# xxxxxx_PCB_Spectrum_Analyzer_x.net
KiCad netlist of a schematic drawn in Altium Designer
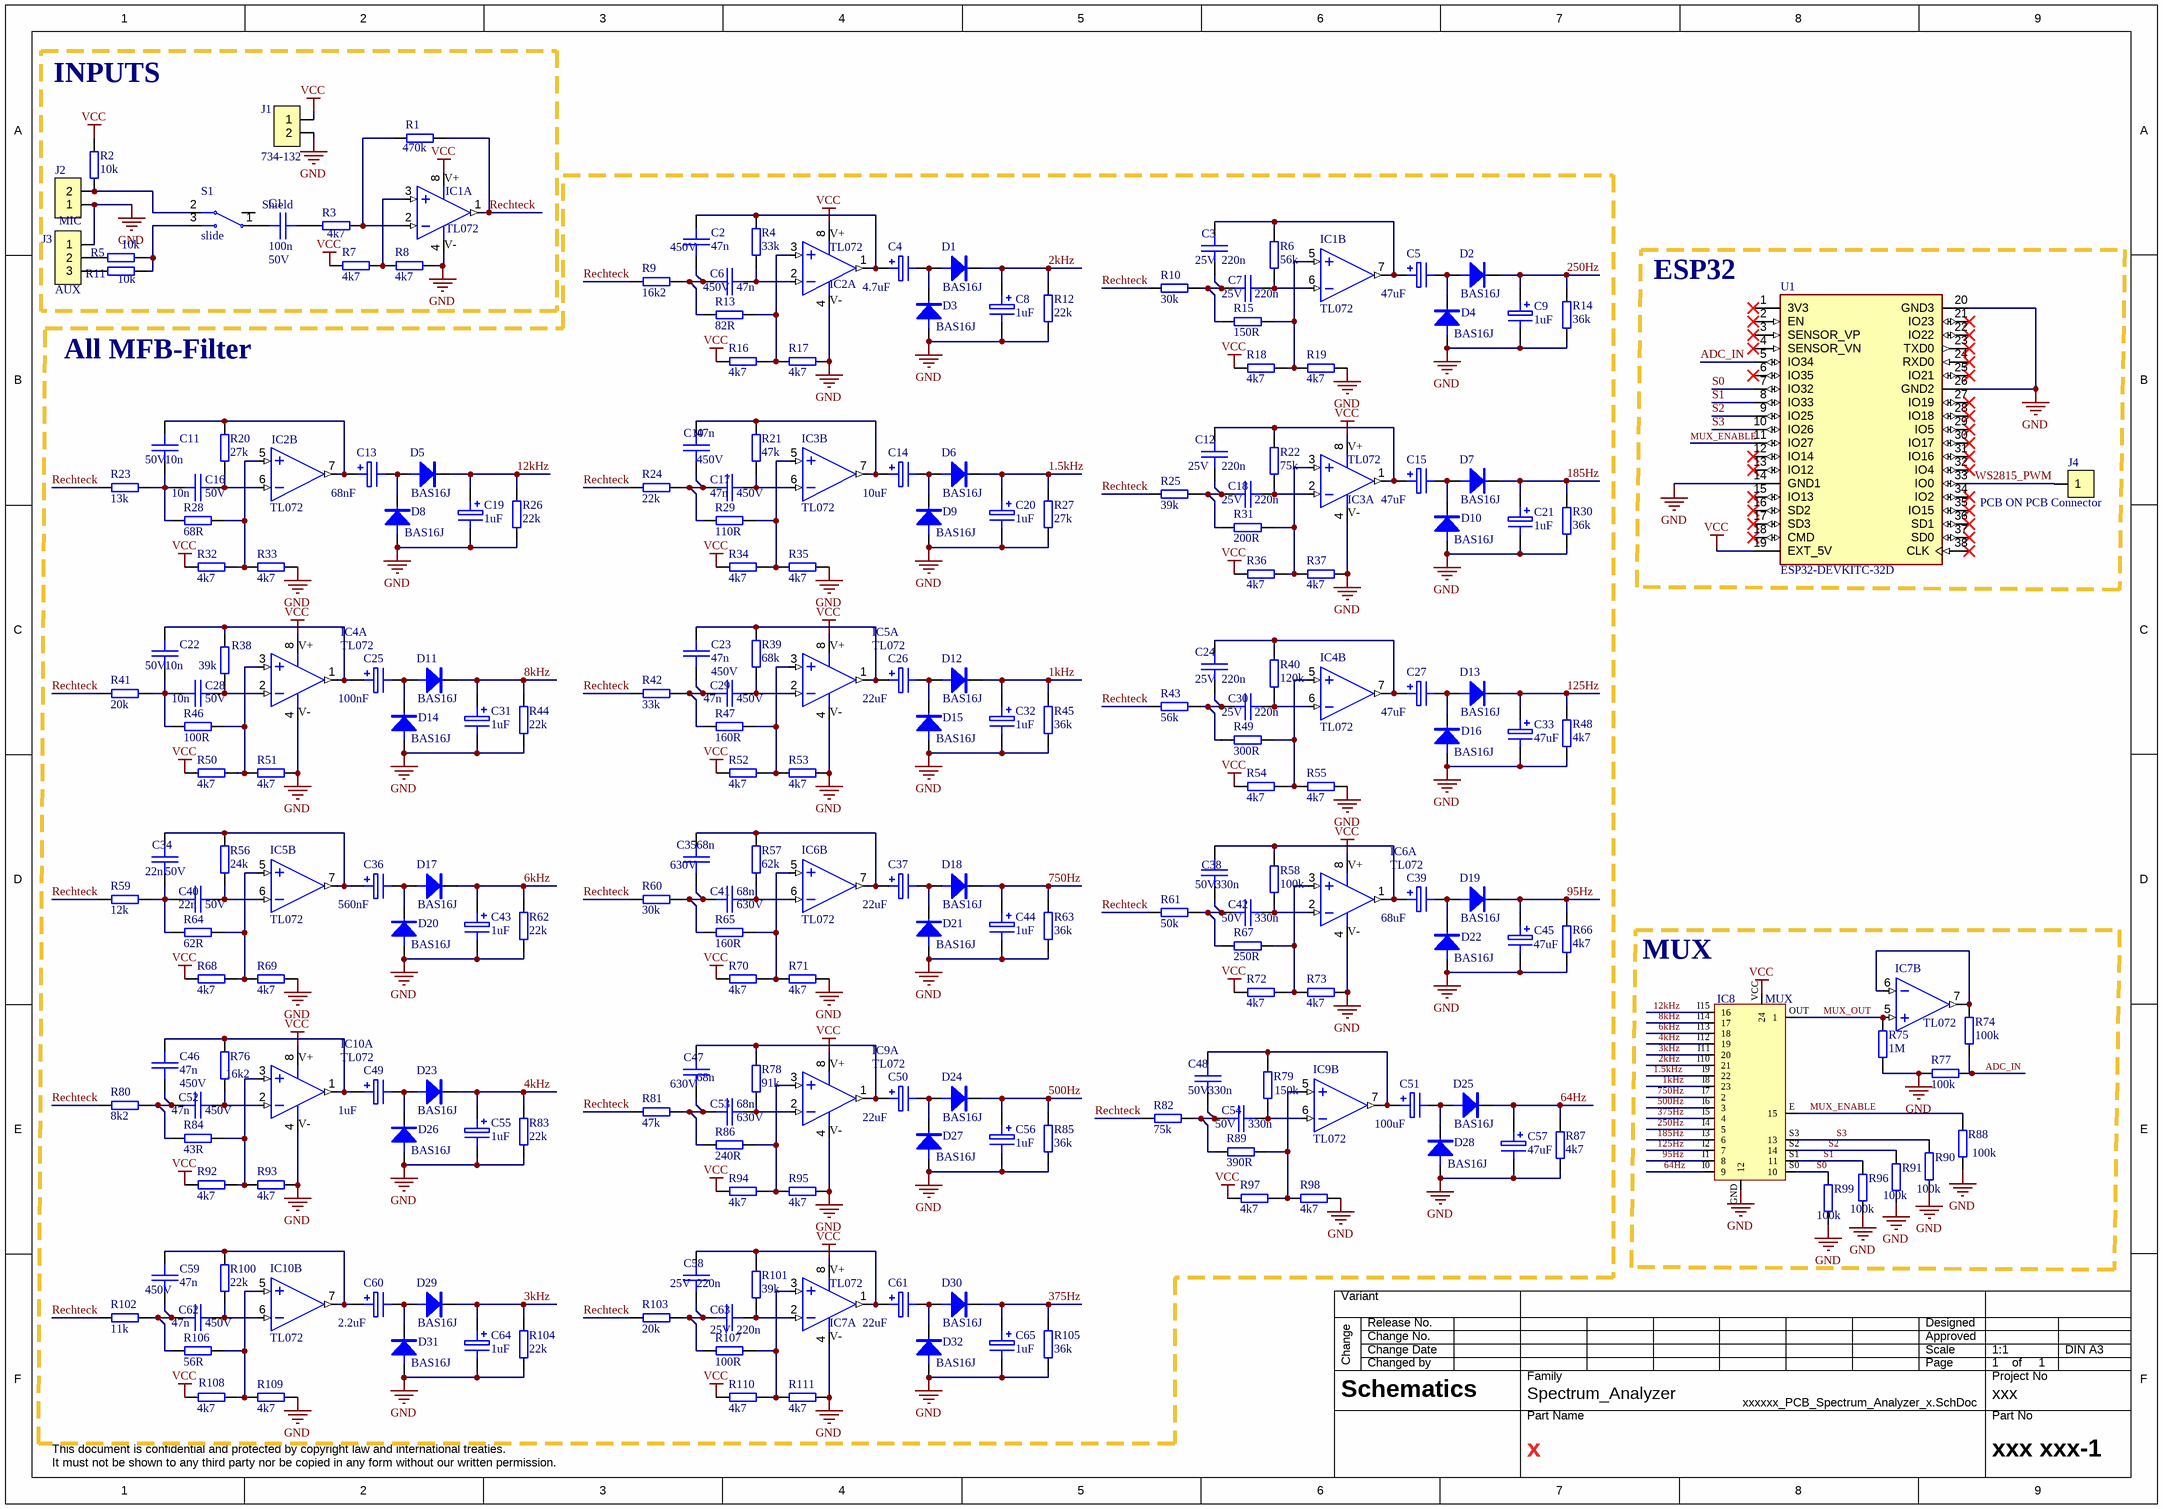
[diagram p0: xxxxxx_PCB_Spectrum_Analyzer_x.SchDoc]

(export (version "E")
  (design (tool "Eeschema 10.0.6"))
  (components
    (comp (ref "C1")
      (value "100n")
      (footprint "C_0805_B")
      (description "C 100n 10% 50V X7R 0805")
      (fields
        (field (name "U") "50V")
        (field (name "PART NUMBER") "301 143")
        (field (name "PUBLISHER") "RKE")
      )
      (libsource (lib "SMD") (part "Capacitor"))
    )
    (comp (ref "C2")
      (value "47n")
      (footprint "C_0805_C")
      (description "C 47n 10% 450V X7T 0805")
      (fields
        (field (name "U") "450V")
        (field (name "PART NUMBER") "302 687")
        (field (name "PUBLISHER") "RKE")
      )
      (libsource (lib "SMD") (part "Capacitor"))
    )
    (comp (ref "C3")
      (value "220n")
      (footprint "C_1206_C")
      (description "C 220n 20% 25V X7R 1206")
      (fields
        (field (name "U") "25V")
        (field (name "PART NUMBER") "301 734")
        (field (name "PUBLISHER") "RKE")
      )
      (libsource (lib "SMD") (part "Capacitor"))
    )
    (comp (ref "C4") (value "4.7uF") (footprint "C 4.7uF") (libsource (lib "4.7 uF") (part "C 4.7uF 450V")))
    (comp (ref "C5") (value "47uF") (footprint "C 4.7uF") (libsource (lib "4.7 uF") (part "C 4.7uF 450V")))
    (comp (ref "C6")
      (value "47n")
      (footprint "C_0805_C")
      (description "C 47n 10% 450V X7T 0805")
      (fields
        (field (name "U") "450V")
        (field (name "PART NUMBER") "302 687")
        (field (name "PUBLISHER") "RKE")
      )
      (libsource (lib "SMD") (part "Capacitor"))
    )
    (comp (ref "C7")
      (value "220n")
      (footprint "C_1206_C")
      (description "C 220n 20% 25V X7R 1206")
      (fields
        (field (name "U") "25V")
        (field (name "PART NUMBER") "301 734")
        (field (name "PUBLISHER") "RKE")
      )
      (libsource (lib "SMD") (part "Capacitor"))
    )
    (comp (ref "C8") (value "1uF") (footprint "C 4.7uF") (libsource (lib "4.7 uF") (part "C 4.7uF 450V")))
    (comp (ref "C9") (value "1uF") (footprint "C 4.7uF") (libsource (lib "4.7 uF") (part "C 4.7uF 450V")))
    (comp (ref "C10")
      (value "47n")
      (footprint "C_0805_C")
      (description "C 47n 10% 450V X7T 0805")
      (fields
        (field (name "U") "450V")
        (field (name "PART NUMBER") "302 687")
        (field (name "PUBLISHER") "RKE")
      )
      (libsource (lib "SMD") (part "Capacitor"))
    )
    (comp (ref "C11")
      (value "10n")
      (footprint "C_0805_B")
      (description "C 10n 10% 50V X7R 0805")
      (fields
        (field (name "U") "50V")
        (field (name "PART NUMBER") "300 130")
        (field (name "PUBLISHER") "RKE")
      )
      (libsource (lib "SMD") (part "Capacitor"))
    )
    (comp (ref "C12")
      (value "220n")
      (footprint "C_1206_C")
      (description "C 220n 20% 25V X7R 1206")
      (fields
        (field (name "U") "25V")
        (field (name "PART NUMBER") "301 734")
        (field (name "PUBLISHER") "RKE")
      )
      (libsource (lib "SMD") (part "Capacitor"))
    )
    (comp (ref "C13") (value "68nF") (footprint "C 4.7uF") (libsource (lib "4.7 uF") (part "C 4.7uF 450V")))
    (comp (ref "C14") (value "10uF") (footprint "C 4.7uF") (libsource (lib "4.7 uF") (part "C 4.7uF 450V")))
    (comp (ref "C15") (value "47uF") (footprint "C 4.7uF") (libsource (lib "4.7 uF") (part "C 4.7uF 450V")))
    (comp (ref "C16")
      (value "10n")
      (footprint "C_0805_B")
      (description "C 10n 10% 50V X7R 0805")
      (fields
        (field (name "U") "50V")
        (field (name "PART NUMBER") "300 130")
        (field (name "PUBLISHER") "RKE")
      )
      (libsource (lib "SMD") (part "Capacitor"))
    )
    (comp (ref "C17")
      (value "47n")
      (footprint "C_0805_C")
      (description "C 47n 10% 450V X7T 0805")
      (fields
        (field (name "U") "450V")
        (field (name "PART NUMBER") "302 687")
        (field (name "PUBLISHER") "RKE")
      )
      (libsource (lib "SMD") (part "Capacitor"))
    )
    (comp (ref "C18")
      (value "220n")
      (footprint "C_1206_C")
      (description "C 220n 20% 25V X7R 1206")
      (fields
        (field (name "U") "25V")
        (field (name "PART NUMBER") "301 734")
        (field (name "PUBLISHER") "RKE")
      )
      (libsource (lib "SMD") (part "Capacitor"))
    )
    (comp (ref "C19") (value "1uF") (footprint "C 4.7uF") (libsource (lib "4.7 uF") (part "C 4.7uF 450V")))
    (comp (ref "C20") (value "1uF") (footprint "C 4.7uF") (libsource (lib "4.7 uF") (part "C 4.7uF 450V")))
    (comp (ref "C21") (value "1uF") (footprint "C 4.7uF") (libsource (lib "4.7 uF") (part "C 4.7uF 450V")))
    (comp (ref "C22")
      (value "10n")
      (footprint "C_0805_B")
      (description "C 10n 10% 50V X7R 0805")
      (fields
        (field (name "U") "50V")
        (field (name "PART NUMBER") "300 130")
        (field (name "PUBLISHER") "RKE")
      )
      (libsource (lib "SMD") (part "Capacitor"))
    )
    (comp (ref "C23")
      (value "47n")
      (footprint "C_0805_C")
      (description "C 47n 10% 450V X7T 0805")
      (fields
        (field (name "U") "450V")
        (field (name "PART NUMBER") "302 687")
        (field (name "PUBLISHER") "RKE")
      )
      (libsource (lib "SMD") (part "Capacitor"))
    )
    (comp (ref "C24")
      (value "220n")
      (footprint "C_1206_C")
      (description "C 220n 20% 25V X7R 1206")
      (fields
        (field (name "U") "25V")
        (field (name "PART NUMBER") "301 734")
        (field (name "PUBLISHER") "RKE")
      )
      (libsource (lib "SMD") (part "Capacitor"))
    )
    (comp (ref "C25") (value "100nF") (footprint "C 4.7uF") (libsource (lib "4.7 uF") (part "C 4.7uF 450V")))
    (comp (ref "C26") (value "22uF") (footprint "C 4.7uF") (libsource (lib "4.7 uF") (part "C 4.7uF 450V")))
    (comp (ref "C27") (value "47uF") (footprint "C 4.7uF") (libsource (lib "4.7 uF") (part "C 4.7uF 450V")))
    (comp (ref "C28")
      (value "10n")
      (footprint "C_0805_B")
      (description "C 10n 10% 50V X7R 0805")
      (fields
        (field (name "U") "50V")
        (field (name "PART NUMBER") "300 130")
        (field (name "PUBLISHER") "RKE")
      )
      (libsource (lib "SMD") (part "Capacitor"))
    )
    (comp (ref "C29")
      (value "47n")
      (footprint "C_0805_C")
      (description "C 47n 10% 450V X7T 0805")
      (fields
        (field (name "U") "450V")
        (field (name "PART NUMBER") "302 687")
        (field (name "PUBLISHER") "RKE")
      )
      (libsource (lib "SMD") (part "Capacitor"))
    )
    (comp (ref "C30")
      (value "220n")
      (footprint "C_1206_C")
      (description "C 220n 20% 25V X7R 1206")
      (fields
        (field (name "U") "25V")
        (field (name "PART NUMBER") "301 734")
        (field (name "PUBLISHER") "RKE")
      )
      (libsource (lib "SMD") (part "Capacitor"))
    )
    (comp (ref "C31") (value "1uF") (footprint "C 4.7uF") (libsource (lib "4.7 uF") (part "C 4.7uF 450V")))
    (comp (ref "C32") (value "1uF") (footprint "C 4.7uF") (libsource (lib "4.7 uF") (part "C 4.7uF 450V")))
    (comp (ref "C33") (value "47uF") (footprint "C 4.7uF") (libsource (lib "4.7 uF") (part "C 4.7uF 450V")))
    (comp (ref "C34")
      (value "22n")
      (footprint "C_0805_A")
      (description "C 22n 10% 50V X7R 0805")
      (fields
        (field (name "U") "50V")
        (field (name "PART NUMBER") "300 131")
        (field (name "PUBLISHER") "RKE")
      )
      (libsource (lib "SMD") (part "Capacitor"))
    )
    (comp (ref "C35")
      (value "68n")
      (footprint "C_1210_D")
      (description "C 68n 20% 630V X7R 1210")
      (fields
        (field (name "U") "630V")
        (field (name "PART NUMBER") "302 807")
        (field (name "PUBLISHER") "RKE")
      )
      (libsource (lib "SMD") (part "Capacitor"))
    )
    (comp (ref "C36") (value "560nF") (footprint "C 4.7uF") (libsource (lib "4.7 uF") (part "C 4.7uF 450V")))
    (comp (ref "C37") (value "22uF") (footprint "C 4.7uF") (libsource (lib "4.7 uF") (part "C 4.7uF 450V")))
    (comp (ref "C38")
      (value "330n")
      (footprint "C_1210_D")
      (description "C 330n 50V X7R 1210")
      (fields
        (field (name "U") "50V")
        (field (name "PART NUMBER") "300 462")
        (field (name "PUBLISHER") "RKE")
      )
      (libsource (lib "SMD") (part "Capacitor"))
    )
    (comp (ref "C39") (value "68uF") (footprint "C 4.7uF") (libsource (lib "4.7 uF") (part "C 4.7uF 450V")))
    (comp (ref "C40")
      (value "22n")
      (footprint "C_0805_A")
      (description "C 22n 10% 50V X7R 0805")
      (fields
        (field (name "U") "50V")
        (field (name "PART NUMBER") "300 131")
        (field (name "PUBLISHER") "RKE")
      )
      (libsource (lib "SMD") (part "Capacitor"))
    )
    (comp (ref "C41")
      (value "68n")
      (footprint "C_1210_D")
      (description "C 68n 20% 630V X7R 1210")
      (fields
        (field (name "U") "630V")
        (field (name "PART NUMBER") "302 807")
        (field (name "PUBLISHER") "RKE")
      )
      (libsource (lib "SMD") (part "Capacitor"))
    )
    (comp (ref "C42")
      (value "330n")
      (footprint "C_1210_D")
      (description "C 330n 50V X7R 1210")
      (fields
        (field (name "U") "50V")
        (field (name "PART NUMBER") "300 462")
        (field (name "PUBLISHER") "RKE")
      )
      (libsource (lib "SMD") (part "Capacitor"))
    )
    (comp (ref "C43") (value "1uF") (footprint "C 4.7uF") (libsource (lib "4.7 uF") (part "C 4.7uF 450V")))
    (comp (ref "C44") (value "1uF") (footprint "C 4.7uF") (libsource (lib "4.7 uF") (part "C 4.7uF 450V")))
    (comp (ref "C45") (value "47uF") (footprint "C 4.7uF") (libsource (lib "4.7 uF") (part "C 4.7uF 450V")))
    (comp (ref "C46")
      (value "47n")
      (footprint "C_0805_C")
      (description "C 47n 10% 450V X7T 0805")
      (fields
        (field (name "U") "450V")
        (field (name "PART NUMBER") "302 687")
        (field (name "PUBLISHER") "RKE")
      )
      (libsource (lib "SMD") (part "Capacitor"))
    )
    (comp (ref "C47")
      (value "68n")
      (footprint "C_1210_D")
      (description "C 68n 20% 630V X7R 1210")
      (fields
        (field (name "U") "630V")
        (field (name "PART NUMBER") "302 807")
        (field (name "PUBLISHER") "RKE")
      )
      (libsource (lib "SMD") (part "Capacitor"))
    )
    (comp (ref "C48")
      (value "330n")
      (footprint "C_1210_D")
      (description "C 330n 50V X7R 1210")
      (fields
        (field (name "U") "50V")
        (field (name "PART NUMBER") "300 462")
        (field (name "PUBLISHER") "RKE")
      )
      (libsource (lib "SMD") (part "Capacitor"))
    )
    (comp (ref "C49") (value "1uF") (footprint "C 4.7uF") (libsource (lib "4.7 uF") (part "C 4.7uF 450V")))
    (comp (ref "C50") (value "22uF") (footprint "C 4.7uF") (libsource (lib "4.7 uF") (part "C 4.7uF 450V")))
    (comp (ref "C51") (value "100uF") (footprint "C 4.7uF") (libsource (lib "4.7 uF") (part "C 4.7uF 450V")))
    (comp (ref "C52")
      (value "47n")
      (footprint "C_0805_C")
      (description "C 47n 10% 450V X7T 0805")
      (fields
        (field (name "U") "450V")
        (field (name "PART NUMBER") "302 687")
        (field (name "PUBLISHER") "RKE")
      )
      (libsource (lib "SMD") (part "Capacitor"))
    )
    (comp (ref "C53")
      (value "68n")
      (footprint "C_1210_D")
      (description "C 68n 20% 630V X7R 1210")
      (fields
        (field (name "U") "630V")
        (field (name "PART NUMBER") "302 807")
        (field (name "PUBLISHER") "RKE")
      )
      (libsource (lib "SMD") (part "Capacitor"))
    )
    (comp (ref "C54")
      (value "330n")
      (footprint "C_1210_D")
      (description "C 330n 50V X7R 1210")
      (fields
        (field (name "U") "50V")
        (field (name "PART NUMBER") "300 462")
        (field (name "PUBLISHER") "RKE")
      )
      (libsource (lib "SMD") (part "Capacitor"))
    )
    (comp (ref "C55") (value "1uF") (footprint "C 4.7uF") (libsource (lib "4.7 uF") (part "C 4.7uF 450V")))
    (comp (ref "C56") (value "1uF") (footprint "C 4.7uF") (libsource (lib "4.7 uF") (part "C 4.7uF 450V")))
    (comp (ref "C57") (value "47uF") (footprint "C 4.7uF") (libsource (lib "4.7 uF") (part "C 4.7uF 450V")))
    (comp (ref "C58")
      (value "220n")
      (footprint "C_1206_C")
      (description "C 220n 20% 25V X7R 1206")
      (fields
        (field (name "U") "25V")
        (field (name "PART NUMBER") "301 734")
        (field (name "PUBLISHER") "RKE")
      )
      (libsource (lib "SMD") (part "Capacitor"))
    )
    (comp (ref "C59")
      (value "47n")
      (footprint "C_0805_C")
      (description "C 47n 10% 450V X7T 0805")
      (fields
        (field (name "U") "450V")
        (field (name "PART NUMBER") "302 687")
        (field (name "PUBLISHER") "RKE")
      )
      (libsource (lib "SMD") (part "Capacitor"))
    )
    (comp (ref "C60") (value "2.2uF") (footprint "C 4.7uF") (libsource (lib "4.7 uF") (part "C 4.7uF 450V")))
    (comp (ref "C61") (value "22uF") (footprint "C 4.7uF") (libsource (lib "4.7 uF") (part "C 4.7uF 450V")))
    (comp (ref "C62")
      (value "47n")
      (footprint "C_0805_C")
      (description "C 47n 10% 450V X7T 0805")
      (fields
        (field (name "U") "450V")
        (field (name "PART NUMBER") "302 687")
        (field (name "PUBLISHER") "RKE")
      )
      (libsource (lib "SMD") (part "Capacitor"))
    )
    (comp (ref "C63")
      (value "220n")
      (footprint "C_1206_C")
      (description "C 220n 20% 25V X7R 1206")
      (fields
        (field (name "U") "25V")
        (field (name "PART NUMBER") "301 734")
        (field (name "PUBLISHER") "RKE")
      )
      (libsource (lib "SMD") (part "Capacitor"))
    )
    (comp (ref "C64") (value "1uF") (footprint "C 4.7uF") (libsource (lib "4.7 uF") (part "C 4.7uF 450V")))
    (comp (ref "C65") (value "1uF") (footprint "C 4.7uF") (libsource (lib "4.7 uF") (part "C 4.7uF 450V")))
    (comp (ref "D1")
      (value "~")
      (footprint "SOD323F")
      (description "D BAS16J 250mA/100V SOD323F")
      (fields
        (field (name "PART") "BAS16J")
        (field (name "PART NUMBER") "303 357")
        (field (name "MANNUFACTURERPARTNUMBER") "BAS16J")
        (field (name "PUBLISHER") "MFL")
      )
      (libsource (lib "SMD") (part "Diode"))
    )
    (comp (ref "D2")
      (value "~")
      (footprint "SOD323F")
      (description "D BAS16J 250mA/100V SOD323F")
      (fields
        (field (name "PART") "BAS16J")
        (field (name "PART NUMBER") "303 357")
        (field (name "MANNUFACTURERPARTNUMBER") "BAS16J")
        (field (name "PUBLISHER") "MFL")
      )
      (libsource (lib "SMD") (part "Diode"))
    )
    (comp (ref "D3")
      (value "~")
      (footprint "SOD323F")
      (description "D BAS16J 250mA/100V SOD323F")
      (fields
        (field (name "PART") "BAS16J")
        (field (name "PART NUMBER") "303 357")
        (field (name "MANNUFACTURERPARTNUMBER") "BAS16J")
        (field (name "PUBLISHER") "MFL")
      )
      (libsource (lib "SMD") (part "Diode"))
    )
    (comp (ref "D4")
      (value "~")
      (footprint "SOD323F")
      (description "D BAS16J 250mA/100V SOD323F")
      (fields
        (field (name "PART") "BAS16J")
        (field (name "PART NUMBER") "303 357")
        (field (name "MANNUFACTURERPARTNUMBER") "BAS16J")
        (field (name "PUBLISHER") "MFL")
      )
      (libsource (lib "SMD") (part "Diode"))
    )
    (comp (ref "D5")
      (value "~")
      (footprint "SOD323F")
      (description "D BAS16J 250mA/100V SOD323F")
      (fields
        (field (name "PART") "BAS16J")
        (field (name "PART NUMBER") "303 357")
        (field (name "MANNUFACTURERPARTNUMBER") "BAS16J")
        (field (name "PUBLISHER") "MFL")
      )
      (libsource (lib "SMD") (part "Diode"))
    )
    (comp (ref "D6")
      (value "~")
      (footprint "SOD323F")
      (description "D BAS16J 250mA/100V SOD323F")
      (fields
        (field (name "PART") "BAS16J")
        (field (name "PART NUMBER") "303 357")
        (field (name "MANNUFACTURERPARTNUMBER") "BAS16J")
        (field (name "PUBLISHER") "MFL")
      )
      (libsource (lib "SMD") (part "Diode"))
    )
    (comp (ref "D7")
      (value "~")
      (footprint "SOD323F")
      (description "D BAS16J 250mA/100V SOD323F")
      (fields
        (field (name "PART") "BAS16J")
        (field (name "PART NUMBER") "303 357")
        (field (name "MANNUFACTURERPARTNUMBER") "BAS16J")
        (field (name "PUBLISHER") "MFL")
      )
      (libsource (lib "SMD") (part "Diode"))
    )
    (comp (ref "D8")
      (value "~")
      (footprint "SOD323F")
      (description "D BAS16J 250mA/100V SOD323F")
      (fields
        (field (name "PART") "BAS16J")
        (field (name "PART NUMBER") "303 357")
        (field (name "MANNUFACTURERPARTNUMBER") "BAS16J")
        (field (name "PUBLISHER") "MFL")
      )
      (libsource (lib "SMD") (part "Diode"))
    )
    (comp (ref "D9")
      (value "~")
      (footprint "SOD323F")
      (description "D BAS16J 250mA/100V SOD323F")
      (fields
        (field (name "PART") "BAS16J")
        (field (name "PART NUMBER") "303 357")
        (field (name "MANNUFACTURERPARTNUMBER") "BAS16J")
        (field (name "PUBLISHER") "MFL")
      )
      (libsource (lib "SMD") (part "Diode"))
    )
    (comp (ref "D10")
      (value "~")
      (footprint "SOD323F")
      (description "D BAS16J 250mA/100V SOD323F")
      (fields
        (field (name "PART") "BAS16J")
        (field (name "PART NUMBER") "303 357")
        (field (name "MANNUFACTURERPARTNUMBER") "BAS16J")
        (field (name "PUBLISHER") "MFL")
      )
      (libsource (lib "SMD") (part "Diode"))
    )
    (comp (ref "D11")
      (value "~")
      (footprint "SOD323F")
      (description "D BAS16J 250mA/100V SOD323F")
      (fields
        (field (name "PART") "BAS16J")
        (field (name "PART NUMBER") "303 357")
        (field (name "MANNUFACTURERPARTNUMBER") "BAS16J")
        (field (name "PUBLISHER") "MFL")
      )
      (libsource (lib "SMD") (part "Diode"))
    )
    (comp (ref "D12")
      (value "~")
      (footprint "SOD323F")
      (description "D BAS16J 250mA/100V SOD323F")
      (fields
        (field (name "PART") "BAS16J")
        (field (name "PART NUMBER") "303 357")
        (field (name "MANNUFACTURERPARTNUMBER") "BAS16J")
        (field (name "PUBLISHER") "MFL")
      )
      (libsource (lib "SMD") (part "Diode"))
    )
    (comp (ref "D13")
      (value "~")
      (footprint "SOD323F")
      (description "D BAS16J 250mA/100V SOD323F")
      (fields
        (field (name "PART") "BAS16J")
        (field (name "PART NUMBER") "303 357")
        (field (name "MANNUFACTURERPARTNUMBER") "BAS16J")
        (field (name "PUBLISHER") "MFL")
      )
      (libsource (lib "SMD") (part "Diode"))
    )
    (comp (ref "D14")
      (value "~")
      (footprint "SOD323F")
      (description "D BAS16J 250mA/100V SOD323F")
      (fields
        (field (name "PART") "BAS16J")
        (field (name "PART NUMBER") "303 357")
        (field (name "MANNUFACTURERPARTNUMBER") "BAS16J")
        (field (name "PUBLISHER") "MFL")
      )
      (libsource (lib "SMD") (part "Diode"))
    )
    (comp (ref "D15")
      (value "~")
      (footprint "SOD323F")
      (description "D BAS16J 250mA/100V SOD323F")
      (fields
        (field (name "PART") "BAS16J")
        (field (name "PART NUMBER") "303 357")
        (field (name "MANNUFACTURERPARTNUMBER") "BAS16J")
        (field (name "PUBLISHER") "MFL")
      )
      (libsource (lib "SMD") (part "Diode"))
    )
    (comp (ref "D16")
      (value "~")
      (footprint "SOD323F")
      (description "D BAS16J 250mA/100V SOD323F")
      (fields
        (field (name "PART") "BAS16J")
        (field (name "PART NUMBER") "303 357")
        (field (name "MANNUFACTURERPARTNUMBER") "BAS16J")
        (field (name "PUBLISHER") "MFL")
      )
      (libsource (lib "SMD") (part "Diode"))
    )
    (comp (ref "D17")
      (value "~")
      (footprint "SOD323F")
      (description "D BAS16J 250mA/100V SOD323F")
      (fields
        (field (name "PART") "BAS16J")
        (field (name "PART NUMBER") "303 357")
        (field (name "MANNUFACTURERPARTNUMBER") "BAS16J")
        (field (name "PUBLISHER") "MFL")
      )
      (libsource (lib "SMD") (part "Diode"))
    )
    (comp (ref "D18")
      (value "~")
      (footprint "SOD323F")
      (description "D BAS16J 250mA/100V SOD323F")
      (fields
        (field (name "PART") "BAS16J")
        (field (name "PART NUMBER") "303 357")
        (field (name "MANNUFACTURERPARTNUMBER") "BAS16J")
        (field (name "PUBLISHER") "MFL")
      )
      (libsource (lib "SMD") (part "Diode"))
    )
    (comp (ref "D19")
      (value "~")
      (footprint "SOD323F")
      (description "D BAS16J 250mA/100V SOD323F")
      (fields
        (field (name "PART") "BAS16J")
        (field (name "PART NUMBER") "303 357")
        (field (name "MANNUFACTURERPARTNUMBER") "BAS16J")
        (field (name "PUBLISHER") "MFL")
      )
      (libsource (lib "SMD") (part "Diode"))
    )
    (comp (ref "D20")
      (value "~")
      (footprint "SOD323F")
      (description "D BAS16J 250mA/100V SOD323F")
      (fields
        (field (name "PART") "BAS16J")
        (field (name "PART NUMBER") "303 357")
        (field (name "MANNUFACTURERPARTNUMBER") "BAS16J")
        (field (name "PUBLISHER") "MFL")
      )
      (libsource (lib "SMD") (part "Diode"))
    )
    (comp (ref "D21")
      (value "~")
      (footprint "SOD323F")
      (description "D BAS16J 250mA/100V SOD323F")
      (fields
        (field (name "PART") "BAS16J")
        (field (name "PART NUMBER") "303 357")
        (field (name "MANNUFACTURERPARTNUMBER") "BAS16J")
        (field (name "PUBLISHER") "MFL")
      )
      (libsource (lib "SMD") (part "Diode"))
    )
    (comp (ref "D22")
      (value "~")
      (footprint "SOD323F")
      (description "D BAS16J 250mA/100V SOD323F")
      (fields
        (field (name "PART") "BAS16J")
        (field (name "PART NUMBER") "303 357")
        (field (name "MANNUFACTURERPARTNUMBER") "BAS16J")
        (field (name "PUBLISHER") "MFL")
      )
      (libsource (lib "SMD") (part "Diode"))
    )
    (comp (ref "D23")
      (value "~")
      (footprint "SOD323F")
      (description "D BAS16J 250mA/100V SOD323F")
      (fields
        (field (name "PART") "BAS16J")
        (field (name "PART NUMBER") "303 357")
        (field (name "MANNUFACTURERPARTNUMBER") "BAS16J")
        (field (name "PUBLISHER") "MFL")
      )
      (libsource (lib "SMD") (part "Diode"))
    )
    (comp (ref "D24")
      (value "~")
      (footprint "SOD323F")
      (description "D BAS16J 250mA/100V SOD323F")
      (fields
        (field (name "PART") "BAS16J")
        (field (name "PART NUMBER") "303 357")
        (field (name "MANNUFACTURERPARTNUMBER") "BAS16J")
        (field (name "PUBLISHER") "MFL")
      )
      (libsource (lib "SMD") (part "Diode"))
    )
    (comp (ref "D25")
      (value "~")
      (footprint "SOD323F")
      (description "D BAS16J 250mA/100V SOD323F")
      (fields
        (field (name "PART") "BAS16J")
        (field (name "PART NUMBER") "303 357")
        (field (name "MANNUFACTURERPARTNUMBER") "BAS16J")
        (field (name "PUBLISHER") "MFL")
      )
      (libsource (lib "SMD") (part "Diode"))
    )
    (comp (ref "D26")
      (value "~")
      (footprint "SOD323F")
      (description "D BAS16J 250mA/100V SOD323F")
      (fields
        (field (name "PART") "BAS16J")
        (field (name "PART NUMBER") "303 357")
        (field (name "MANNUFACTURERPARTNUMBER") "BAS16J")
        (field (name "PUBLISHER") "MFL")
      )
      (libsource (lib "SMD") (part "Diode"))
    )
    (comp (ref "D27")
      (value "~")
      (footprint "SOD323F")
      (description "D BAS16J 250mA/100V SOD323F")
      (fields
        (field (name "PART") "BAS16J")
        (field (name "PART NUMBER") "303 357")
        (field (name "MANNUFACTURERPARTNUMBER") "BAS16J")
        (field (name "PUBLISHER") "MFL")
      )
      (libsource (lib "SMD") (part "Diode"))
    )
    (comp (ref "D28")
      (value "~")
      (footprint "SOD323F")
      (description "D BAS16J 250mA/100V SOD323F")
      (fields
        (field (name "PART") "BAS16J")
        (field (name "PART NUMBER") "303 357")
        (field (name "MANNUFACTURERPARTNUMBER") "BAS16J")
        (field (name "PUBLISHER") "MFL")
      )
      (libsource (lib "SMD") (part "Diode"))
    )
    (comp (ref "D29")
      (value "~")
      (footprint "SOD323F")
      (description "D BAS16J 250mA/100V SOD323F")
      (fields
        (field (name "PART") "BAS16J")
        (field (name "PART NUMBER") "303 357")
        (field (name "MANNUFACTURERPARTNUMBER") "BAS16J")
        (field (name "PUBLISHER") "MFL")
      )
      (libsource (lib "SMD") (part "Diode"))
    )
    (comp (ref "D30")
      (value "~")
      (footprint "SOD323F")
      (description "D BAS16J 250mA/100V SOD323F")
      (fields
        (field (name "PART") "BAS16J")
        (field (name "PART NUMBER") "303 357")
        (field (name "MANNUFACTURERPARTNUMBER") "BAS16J")
        (field (name "PUBLISHER") "MFL")
      )
      (libsource (lib "SMD") (part "Diode"))
    )
    (comp (ref "D31")
      (value "~")
      (footprint "SOD323F")
      (description "D BAS16J 250mA/100V SOD323F")
      (fields
        (field (name "PART") "BAS16J")
        (field (name "PART NUMBER") "303 357")
        (field (name "MANNUFACTURERPARTNUMBER") "BAS16J")
        (field (name "PUBLISHER") "MFL")
      )
      (libsource (lib "SMD") (part "Diode"))
    )
    (comp (ref "D32")
      (value "~")
      (footprint "SOD323F")
      (description "D BAS16J 250mA/100V SOD323F")
      (fields
        (field (name "PART") "BAS16J")
        (field (name "PART NUMBER") "303 357")
        (field (name "MANNUFACTURERPARTNUMBER") "BAS16J")
        (field (name "PUBLISHER") "MFL")
      )
      (libsource (lib "SMD") (part "Diode"))
    )
    (comp (ref "IC1")
      (value "TL072")
      (footprint "SO8_A")
      (description "IC TL072 OpAmp -40°..+85°C SO8")
      (fields (field (name "PART NUMBER") "300 454") (field (name "PUBLISHER") "RKE"))
      (libsource (lib "SMD") (part "OPAMP_Dual"))
    )
    (comp (ref "IC2")
      (value "TL072")
      (footprint "SO8_A")
      (description "IC TL072 OpAmp -40°..+85°C SO8")
      (fields (field (name "PART NUMBER") "300 454") (field (name "PUBLISHER") "RKE"))
      (libsource (lib "SMD") (part "OPAMP_Dual"))
    )
    (comp (ref "IC3")
      (value "TL072")
      (footprint "SO8_A")
      (description "IC TL072 OpAmp -40°..+85°C SO8")
      (fields (field (name "PART NUMBER") "300 454") (field (name "PUBLISHER") "RKE"))
      (libsource (lib "SMD") (part "OPAMP_Dual"))
    )
    (comp (ref "IC4")
      (value "TL072")
      (footprint "SO8_A")
      (description "IC TL072 OpAmp -40°..+85°C SO8")
      (fields (field (name "PART NUMBER") "300 454") (field (name "PUBLISHER") "RKE"))
      (libsource (lib "SMD") (part "OPAMP_Dual"))
    )
    (comp (ref "IC5")
      (value "TL072")
      (footprint "SO8_A")
      (description "IC TL072 OpAmp -40°..+85°C SO8")
      (fields (field (name "PART NUMBER") "300 454") (field (name "PUBLISHER") "RKE"))
      (libsource (lib "SMD") (part "OPAMP_Dual"))
    )
    (comp (ref "IC6")
      (value "TL072")
      (footprint "SO8_A")
      (description "IC TL072 OpAmp -40°..+85°C SO8")
      (fields (field (name "PART NUMBER") "300 454") (field (name "PUBLISHER") "RKE"))
      (libsource (lib "SMD") (part "OPAMP_Dual"))
    )
    (comp (ref "IC7")
      (value "TL072")
      (footprint "SO8_A")
      (description "IC TL072 OpAmp -40°..+85°C SO8")
      (fields (field (name "PART NUMBER") "300 454") (field (name "PUBLISHER") "RKE"))
      (libsource (lib "SMD") (part "OPAMP_Dual"))
    )
    (comp (ref "IC8")
      (value "MUX")
      (footprint "MUX:MUX")
      (description "Analog MUX 16-Bit")
      (libsource (lib "MUX") (part "MUX"))
    )
    (comp (ref "IC9")
      (value "TL072")
      (footprint "SO8_A")
      (description "IC TL072 OpAmp -40°..+85°C SO8")
      (fields (field (name "PART NUMBER") "300 454") (field (name "PUBLISHER") "RKE"))
      (libsource (lib "SMD") (part "OPAMP_Dual"))
    )
    (comp (ref "IC10")
      (value "TL072")
      (footprint "SO8_A")
      (description "IC TL072 OpAmp -40°..+85°C SO8")
      (fields (field (name "PART NUMBER") "300 454") (field (name "PUBLISHER") "RKE"))
      (libsource (lib "SMD") (part "OPAMP_Dual"))
    )
    (comp (ref "J1")
      (value "734-132")
      (footprint "734-132")
      (description "J Header m 0° 2p 3.5mm")
      (fields (field (name "PART NUMBER") "301 939") (field (name "PUBLISHER") "MFL"))
      (libsource (lib "") (part "Connector2Pin_1"))
    )
    (comp (ref "J2")
      (value "MIC")
      (footprint "734-132")
      (description "J Header m 0° 2p 3.5mm")
      (fields (field (name "PART NUMBER") "301 939") (field (name "PUBLISHER") "MFL"))
      (libsource (lib "KONV") (part "Connector2Pin"))
    )
    (comp (ref "J3")
      (value "AUX")
      (footprint "734-133")
      (description "J Header m 0° 3p 3.5mm")
      (fields (field (name "PART NUMBER") "301 940") (field (name "PUBLISHER") "MFL"))
      (libsource (lib "KONV") (part "Connector3Pin"))
    )
    (comp (ref "J4")
      (value "PCB ON PCB Connector")
      (footprint "PCBConnectorPad")
      (fields (field (name "PUBLISHER") "RKE"))
      (libsource (lib "PRE") (part "Connector1Pin"))
    )
    (comp (ref "R1")
      (value "470k")
      (footprint "R_0805_A")
      (description "R 560k 5% 125mW 0805")
      (fields (field (name "PART NUMBER") "300 093") (field (name "PUBLISHER") "MFL"))
      (libsource (lib "SMD") (part "Resistor"))
    )
    (comp (ref "R2")
      (value "10k")
      (footprint "R_0805_A")
      (description "R 4k7 1% 125mW 0805")
      (fields (field (name "PART NUMBER") "300 079") (field (name "PUBLISHER") "RKE"))
      (libsource (lib "SMD") (part "Resistor"))
    )
    (comp (ref "R3")
      (value "4k7")
      (footprint "R_0805_A")
      (description "R 4k7 1% 125mW 0805")
      (fields (field (name "PART NUMBER") "300 079") (field (name "PUBLISHER") "RKE"))
      (libsource (lib "SMD") (part "Resistor"))
    )
    (comp (ref "R4")
      (value "33k")
      (footprint "R_0805_A")
      (description "R 33k 5% 125mW 0805")
      (fields (field (name "PART NUMBER") "300 435") (field (name "PUBLISHER") "MFL"))
      (libsource (lib "SMD") (part "Resistor"))
    )
    (comp (ref "R5")
      (value "10k")
      (footprint "R_0805_A")
      (description "R 4k7 1% 125mW 0805")
      (fields (field (name "PART NUMBER") "300 079") (field (name "PUBLISHER") "RKE"))
      (libsource (lib "SMD") (part "Resistor"))
    )
    (comp (ref "R6")
      (value "56k")
      (footprint "R_0805_A")
      (description "R 56k 1% 125mW 0805")
      (fields (field (name "PART NUMBER") "302 780") (field (name "PUBLISHER") "MFL"))
      (libsource (lib "SMD") (part "Resistor"))
    )
    (comp (ref "R7")
      (value "4k7")
      (footprint "R_0805_A")
      (description "R 4k7 1% 125mW 0805")
      (fields (field (name "PART NUMBER") "300 079") (field (name "PUBLISHER") "RKE"))
      (libsource (lib "SMD") (part "Resistor"))
    )
    (comp (ref "R8")
      (value "4k7")
      (footprint "R_0805_A")
      (description "R 4k7 1% 125mW 0805")
      (fields (field (name "PART NUMBER") "300 079") (field (name "PUBLISHER") "RKE"))
      (libsource (lib "SMD") (part "Resistor"))
    )
    (comp (ref "R9")
      (value "16k2")
      (footprint "R_0805_A")
      (description "R 15k 5% 125mW 0805")
      (fields (field (name "PART NUMBER") "300 849") (field (name "PUBLISHER") "MFL"))
      (libsource (lib "SMD") (part "Resistor"))
    )
    (comp (ref "R10")
      (value "30k")
      (footprint "R_0805_A")
      (description "R 33k 5% 125mW 0805")
      (fields (field (name "PART NUMBER") "300 435") (field (name "PUBLISHER") "MFL"))
      (libsource (lib "SMD") (part "Resistor"))
    )
    (comp (ref "R11")
      (value "10k")
      (footprint "R_0805_A")
      (description "R 4k7 1% 125mW 0805")
      (fields (field (name "PART NUMBER") "300 079") (field (name "PUBLISHER") "RKE"))
      (libsource (lib "SMD") (part "Resistor"))
    )
    (comp (ref "R12")
      (value "22k")
      (footprint "R_0805_A")
      (description "R 27k 5% 125mW 0805")
      (fields (field (name "PART NUMBER") "300 083") (field (name "PUBLISHER") "MFL"))
      (libsource (lib "SMD") (part "Resistor"))
    )
    (comp (ref "R13")
      (value "82R")
      (footprint "R_0805_A")
      (description "R 75R 1% 125mW 0805")
      (fields (field (name "PART NUMBER") "303 408") (field (name "PUBLISHER") "MFL"))
      (libsource (lib "SMD") (part "Resistor"))
    )
    (comp (ref "R14")
      (value "36k")
      (footprint "R_0805_A")
      (description "R 27k 5% 125mW 0805")
      (fields (field (name "PART NUMBER") "300 083") (field (name "PUBLISHER") "MFL"))
      (libsource (lib "SMD") (part "Resistor"))
    )
    (comp (ref "R15")
      (value "150R")
      (footprint "R_0805_A")
      (description "R 150R 5% 125mW 0805")
      (fields (field (name "PART NUMBER") "302 203") (field (name "PUBLISHER") "MFL"))
      (libsource (lib "SMD") (part "Resistor"))
    )
    (comp (ref "R16")
      (value "4k7")
      (footprint "R_0805_A")
      (description "R 4k7 1% 125mW 0805")
      (fields (field (name "PART NUMBER") "300 079") (field (name "PUBLISHER") "RKE"))
      (libsource (lib "SMD") (part "Resistor"))
    )
    (comp (ref "R17")
      (value "4k7")
      (footprint "R_0805_A")
      (description "R 4k7 1% 125mW 0805")
      (fields (field (name "PART NUMBER") "300 079") (field (name "PUBLISHER") "RKE"))
      (libsource (lib "SMD") (part "Resistor"))
    )
    (comp (ref "R18")
      (value "4k7")
      (footprint "R_0805_A")
      (description "R 4k7 1% 125mW 0805")
      (fields (field (name "PART NUMBER") "300 079") (field (name "PUBLISHER") "RKE"))
      (libsource (lib "SMD") (part "Resistor"))
    )
    (comp (ref "R19")
      (value "4k7")
      (footprint "R_0805_A")
      (description "R 4k7 1% 125mW 0805")
      (fields (field (name "PART NUMBER") "300 079") (field (name "PUBLISHER") "RKE"))
      (libsource (lib "SMD") (part "Resistor"))
    )
    (comp (ref "R20")
      (value "27k")
      (footprint "R_0805_A")
      (description "R 27k 5% 125mW 0805")
      (fields (field (name "PART NUMBER") "300 083") (field (name "PUBLISHER") "MFL"))
      (libsource (lib "SMD") (part "Resistor"))
    )
    (comp (ref "R21")
      (value "47k")
      (footprint "R_0805_A")
      (description "R 47k 5% 125mW 0805")
      (fields (field (name "PART NUMBER") "300 084") (field (name "PUBLISHER") "MFL"))
      (libsource (lib "SMD") (part "Resistor"))
    )
    (comp (ref "R22")
      (value "75k")
      (footprint "R_0805_A")
      (description "R 75R 1% 125mW 0805")
      (fields (field (name "PART NUMBER") "303 408") (field (name "PUBLISHER") "MFL"))
      (libsource (lib "SMD") (part "Resistor"))
    )
    (comp (ref "R23")
      (value "13k")
      (footprint "R_0402_A")
      (description "R 13k 1% 63mW 0402")
      (fields (field (name "PART NUMBER") "303 285") (field (name "PUBLISHER") "MFL"))
      (libsource (lib "SMD") (part "Resistor"))
    )
    (comp (ref "R24")
      (value "22k")
      (footprint "R_0805_A")
      (description "R 22k 5% 125mW 0805")
      (fields (field (name "PART NUMBER") "300 082") (field (name "PUBLISHER") "MFL"))
      (libsource (lib "SMD") (part "Resistor"))
    )
    (comp (ref "R25")
      (value "39k")
      (footprint "R_0805_A")
      (description "R 33k 5% 125mW 0805")
      (fields (field (name "PART NUMBER") "300 435") (field (name "PUBLISHER") "MFL"))
      (libsource (lib "SMD") (part "Resistor"))
    )
    (comp (ref "R26")
      (value "22k")
      (footprint "R_0805_A")
      (description "R 27k 5% 125mW 0805")
      (fields (field (name "PART NUMBER") "300 083") (field (name "PUBLISHER") "MFL"))
      (libsource (lib "SMD") (part "Resistor"))
    )
    (comp (ref "R27")
      (value "27k")
      (footprint "R_0805_A")
      (description "R 27k 5% 125mW 0805")
      (fields (field (name "PART NUMBER") "300 083") (field (name "PUBLISHER") "MFL"))
      (libsource (lib "SMD") (part "Resistor"))
    )
    (comp (ref "R28")
      (value "68R")
      (footprint "R_0805_A")
      (description "R 68k 1% 125mW 0805")
      (fields (field (name "PART NUMBER") "300 086") (field (name "PUBLISHER") "MFL"))
      (libsource (lib "SMD") (part "Resistor"))
    )
    (comp (ref "R29")
      (value "110R")
      (footprint "R_0805_A")
      (description "R 100R 1% 125mW 0805")
      (fields (field (name "PART NUMBER") "300 069") (field (name "PUBLISHER") "RKE"))
      (libsource (lib "SMD") (part "Resistor"))
    )
    (comp (ref "R30")
      (value "36k")
      (footprint "R_0805_A")
      (description "R 27k 5% 125mW 0805")
      (fields (field (name "PART NUMBER") "300 083") (field (name "PUBLISHER") "MFL"))
      (libsource (lib "SMD") (part "Resistor"))
    )
    (comp (ref "R31")
      (value "200R")
      (footprint "R_0805_A")
      (description "R 220R 1% 125mW 0805")
      (fields (field (name "PART NUMBER") "300 917") (field (name "PUBLISHER") "MFL"))
      (libsource (lib "SMD") (part "Resistor"))
    )
    (comp (ref "R32")
      (value "4k7")
      (footprint "R_0805_A")
      (description "R 4k7 1% 125mW 0805")
      (fields (field (name "PART NUMBER") "300 079") (field (name "PUBLISHER") "RKE"))
      (libsource (lib "SMD") (part "Resistor"))
    )
    (comp (ref "R33")
      (value "4k7")
      (footprint "R_0805_A")
      (description "R 4k7 1% 125mW 0805")
      (fields (field (name "PART NUMBER") "300 079") (field (name "PUBLISHER") "RKE"))
      (libsource (lib "SMD") (part "Resistor"))
    )
    (comp (ref "R34")
      (value "4k7")
      (footprint "R_0805_A")
      (description "R 4k7 1% 125mW 0805")
      (fields (field (name "PART NUMBER") "300 079") (field (name "PUBLISHER") "RKE"))
      (libsource (lib "SMD") (part "Resistor"))
    )
    (comp (ref "R35")
      (value "4k7")
      (footprint "R_0805_A")
      (description "R 4k7 1% 125mW 0805")
      (fields (field (name "PART NUMBER") "300 079") (field (name "PUBLISHER") "RKE"))
      (libsource (lib "SMD") (part "Resistor"))
    )
    (comp (ref "R36")
      (value "4k7")
      (footprint "R_0805_A")
      (description "R 4k7 1% 125mW 0805")
      (fields (field (name "PART NUMBER") "300 079") (field (name "PUBLISHER") "RKE"))
      (libsource (lib "SMD") (part "Resistor"))
    )
    (comp (ref "R37")
      (value "4k7")
      (footprint "R_0805_A")
      (description "R 4k7 1% 125mW 0805")
      (fields (field (name "PART NUMBER") "300 079") (field (name "PUBLISHER") "RKE"))
      (libsource (lib "SMD") (part "Resistor"))
    )
    (comp (ref "R38")
      (value "39k")
      (footprint "R_0805_A")
      (description "R 12k 5% 125mW 0805")
      (fields (field (name "PART NUMBER") "300 081") (field (name "PUBLISHER") "MFL"))
      (libsource (lib "SMD") (part "Resistor"))
    )
    (comp (ref "R39")
      (value "68k")
      (footprint "R_0805_A")
      (description "R 68k 1% 125mW 0805")
      (fields (field (name "PART NUMBER") "300 086") (field (name "PUBLISHER") "MFL"))
      (libsource (lib "SMD") (part "Resistor"))
    )
    (comp (ref "R40")
      (value "120k")
      (footprint "R_0805_A")
      (description "R 220R 1% 125mW 0805")
      (fields (field (name "PART NUMBER") "300 917") (field (name "PUBLISHER") "MFL"))
      (libsource (lib "SMD") (part "Resistor"))
    )
    (comp (ref "R41")
      (value "20k")
      (footprint "R_0805_A")
      (description "R 20k 1% 125mW 0805")
      (fields (field (name "PART NUMBER") "300 080") (field (name "PUBLISHER") "MFL"))
      (libsource (lib "SMD") (part "Resistor"))
    )
    (comp (ref "R42")
      (value "33k")
      (footprint "R_0805_A")
      (description "R 33k 5% 125mW 0805")
      (fields (field (name "PART NUMBER") "300 435") (field (name "PUBLISHER") "MFL"))
      (libsource (lib "SMD") (part "Resistor"))
    )
    (comp (ref "R43")
      (value "56k")
      (footprint "R_0805_A")
      (description "R 220R 1% 125mW 0805")
      (fields (field (name "PART NUMBER") "300 917") (field (name "PUBLISHER") "MFL"))
      (libsource (lib "SMD") (part "Resistor"))
    )
    (comp (ref "R44")
      (value "22k")
      (footprint "R_0805_A")
      (description "R 27k 5% 125mW 0805")
      (fields (field (name "PART NUMBER") "300 083") (field (name "PUBLISHER") "MFL"))
      (libsource (lib "SMD") (part "Resistor"))
    )
    (comp (ref "R45")
      (value "36k")
      (footprint "R_0805_A")
      (description "R 27k 5% 125mW 0805")
      (fields (field (name "PART NUMBER") "300 083") (field (name "PUBLISHER") "MFL"))
      (libsource (lib "SMD") (part "Resistor"))
    )
    (comp (ref "R46")
      (value "100R")
      (footprint "R_0805_A")
      (description "R 100R 1% 125mW 0805")
      (fields (field (name "PART NUMBER") "300 069") (field (name "PUBLISHER") "RKE"))
      (libsource (lib "SMD") (part "Resistor"))
    )
    (comp (ref "R47")
      (value "160R")
      (footprint "R_0805_A")
      (description "R 150R 5% 125mW 0805")
      (fields (field (name "PART NUMBER") "302 203") (field (name "PUBLISHER") "MFL"))
      (libsource (lib "SMD") (part "Resistor"))
    )
    (comp (ref "R48")
      (value "4k7")
      (footprint "R_0805_A")
      (description "R 27k 5% 125mW 0805")
      (fields (field (name "PART NUMBER") "300 083") (field (name "PUBLISHER") "MFL"))
      (libsource (lib "SMD") (part "Resistor"))
    )
    (comp (ref "R49")
      (value "300R")
      (footprint "R_0805_A")
      (description "R 220R 1% 125mW 0805")
      (fields (field (name "PART NUMBER") "300 917") (field (name "PUBLISHER") "MFL"))
      (libsource (lib "SMD") (part "Resistor"))
    )
    (comp (ref "R50")
      (value "4k7")
      (footprint "R_0805_A")
      (description "R 4k7 1% 125mW 0805")
      (fields (field (name "PART NUMBER") "300 079") (field (name "PUBLISHER") "RKE"))
      (libsource (lib "SMD") (part "Resistor"))
    )
    (comp (ref "R51")
      (value "4k7")
      (footprint "R_0805_A")
      (description "R 4k7 1% 125mW 0805")
      (fields (field (name "PART NUMBER") "300 079") (field (name "PUBLISHER") "RKE"))
      (libsource (lib "SMD") (part "Resistor"))
    )
    (comp (ref "R52")
      (value "4k7")
      (footprint "R_0805_A")
      (description "R 4k7 1% 125mW 0805")
      (fields (field (name "PART NUMBER") "300 079") (field (name "PUBLISHER") "RKE"))
      (libsource (lib "SMD") (part "Resistor"))
    )
    (comp (ref "R53")
      (value "4k7")
      (footprint "R_0805_A")
      (description "R 4k7 1% 125mW 0805")
      (fields (field (name "PART NUMBER") "300 079") (field (name "PUBLISHER") "RKE"))
      (libsource (lib "SMD") (part "Resistor"))
    )
    (comp (ref "R54")
      (value "4k7")
      (footprint "R_0805_A")
      (description "R 4k7 1% 125mW 0805")
      (fields (field (name "PART NUMBER") "300 079") (field (name "PUBLISHER") "RKE"))
      (libsource (lib "SMD") (part "Resistor"))
    )
    (comp (ref "R55")
      (value "4k7")
      (footprint "R_0805_A")
      (description "R 4k7 1% 125mW 0805")
      (fields (field (name "PART NUMBER") "300 079") (field (name "PUBLISHER") "RKE"))
      (libsource (lib "SMD") (part "Resistor"))
    )
    (comp (ref "R56")
      (value "24k")
      (footprint "R_0805_A")
      (description "R 22k 5% 125mW 0805")
      (fields (field (name "PART NUMBER") "300 082") (field (name "PUBLISHER") "MFL"))
      (libsource (lib "SMD") (part "Resistor"))
    )
    (comp (ref "R57")
      (value "62k")
      (footprint "R_0805_A")
      (description "R 68k 1% 125mW 0805")
      (fields (field (name "PART NUMBER") "300 086") (field (name "PUBLISHER") "MFL"))
      (libsource (lib "SMD") (part "Resistor"))
    )
    (comp (ref "R58")
      (value "100k")
      (footprint "R_0805_A")
      (description "R 220R 1% 125mW 0805")
      (fields (field (name "PART NUMBER") "300 917") (field (name "PUBLISHER") "MFL"))
      (libsource (lib "SMD") (part "Resistor"))
    )
    (comp (ref "R59")
      (value "12k")
      (footprint "R_0805_A")
      (description "R 12k 5% 125mW 0805")
      (fields (field (name "PART NUMBER") "300 081") (field (name "PUBLISHER") "MFL"))
      (libsource (lib "SMD") (part "Resistor"))
    )
    (comp (ref "R60")
      (value "30k")
      (footprint "R_0805_A")
      (description "R 33k 5% 125mW 0805")
      (fields (field (name "PART NUMBER") "300 435") (field (name "PUBLISHER") "MFL"))
      (libsource (lib "SMD") (part "Resistor"))
    )
    (comp (ref "R61")
      (value "50k")
      (footprint "R_0805_A")
      (description "R 220R 1% 125mW 0805")
      (fields (field (name "PART NUMBER") "300 917") (field (name "PUBLISHER") "MFL"))
      (libsource (lib "SMD") (part "Resistor"))
    )
    (comp (ref "R62")
      (value "22k")
      (footprint "R_0805_A")
      (description "R 27k 5% 125mW 0805")
      (fields (field (name "PART NUMBER") "300 083") (field (name "PUBLISHER") "MFL"))
      (libsource (lib "SMD") (part "Resistor"))
    )
    (comp (ref "R63")
      (value "36k")
      (footprint "R_0805_A")
      (description "R 27k 5% 125mW 0805")
      (fields (field (name "PART NUMBER") "300 083") (field (name "PUBLISHER") "MFL"))
      (libsource (lib "SMD") (part "Resistor"))
    )
    (comp (ref "R64")
      (value "62R")
      (footprint "R_0805_A")
      (description "R 62R 1% 125mW 0805")
      (fields (field (name "PART NUMBER") "300 086") (field (name "PUBLISHER") "MFL"))
      (libsource (lib "SMD") (part "Resistor"))
    )
    (comp (ref "R65")
      (value "160R")
      (footprint "R_0805_A")
      (description "R 150R 5% 125mW 0805")
      (fields (field (name "PART NUMBER") "302 203") (field (name "PUBLISHER") "MFL"))
      (libsource (lib "SMD") (part "Resistor"))
    )
    (comp (ref "R66")
      (value "4k7")
      (footprint "R_0805_A")
      (description "R 27k 5% 125mW 0805")
      (fields (field (name "PART NUMBER") "300 083") (field (name "PUBLISHER") "MFL"))
      (libsource (lib "SMD") (part "Resistor"))
    )
    (comp (ref "R67")
      (value "250R")
      (footprint "R_0805_A")
      (description "R 220R 1% 125mW 0805")
      (fields (field (name "PART NUMBER") "300 917") (field (name "PUBLISHER") "MFL"))
      (libsource (lib "SMD") (part "Resistor"))
    )
    (comp (ref "R68")
      (value "4k7")
      (footprint "R_0805_A")
      (description "R 4k7 1% 125mW 0805")
      (fields (field (name "PART NUMBER") "300 079") (field (name "PUBLISHER") "RKE"))
      (libsource (lib "SMD") (part "Resistor"))
    )
    (comp (ref "R69")
      (value "4k7")
      (footprint "R_0805_A")
      (description "R 4k7 1% 125mW 0805")
      (fields (field (name "PART NUMBER") "300 079") (field (name "PUBLISHER") "RKE"))
      (libsource (lib "SMD") (part "Resistor"))
    )
    (comp (ref "R70")
      (value "4k7")
      (footprint "R_0805_A")
      (description "R 4k7 1% 125mW 0805")
      (fields (field (name "PART NUMBER") "300 079") (field (name "PUBLISHER") "RKE"))
      (libsource (lib "SMD") (part "Resistor"))
    )
    (comp (ref "R71")
      (value "4k7")
      (footprint "R_0805_A")
      (description "R 4k7 1% 125mW 0805")
      (fields (field (name "PART NUMBER") "300 079") (field (name "PUBLISHER") "RKE"))
      (libsource (lib "SMD") (part "Resistor"))
    )
    (comp (ref "R72")
      (value "4k7")
      (footprint "R_0805_A")
      (description "R 4k7 1% 125mW 0805")
      (fields (field (name "PART NUMBER") "300 079") (field (name "PUBLISHER") "RKE"))
      (libsource (lib "SMD") (part "Resistor"))
    )
    (comp (ref "R73")
      (value "4k7")
      (footprint "R_0805_A")
      (description "R 4k7 1% 125mW 0805")
      (fields (field (name "PART NUMBER") "300 079") (field (name "PUBLISHER") "RKE"))
      (libsource (lib "SMD") (part "Resistor"))
    )
    (comp (ref "R74")
      (value "100k")
      (footprint "R_0805_A")
      (description "R 27k 5% 125mW 0805")
      (fields (field (name "PART NUMBER") "300 083") (field (name "PUBLISHER") "MFL"))
      (libsource (lib "SMD") (part "Resistor"))
    )
    (comp (ref "R75")
      (value "1M")
      (footprint "R_0805_A")
      (description "R 27k 5% 125mW 0805")
      (fields (field (name "PART NUMBER") "300 083") (field (name "PUBLISHER") "MFL"))
      (libsource (lib "SMD") (part "Resistor"))
    )
    (comp (ref "R76")
      (value "16k2")
      (footprint "R_0805_A")
      (description "R 15k 5% 125mW 0805")
      (fields (field (name "PART NUMBER") "300 849") (field (name "PUBLISHER") "MFL"))
      (libsource (lib "SMD") (part "Resistor"))
    )
    (comp (ref "R77")
      (value "100k")
      (footprint "R_0805_A")
      (description "R 27k 5% 125mW 0805")
      (fields (field (name "PART NUMBER") "300 083") (field (name "PUBLISHER") "MFL"))
      (libsource (lib "SMD") (part "Resistor"))
    )
    (comp (ref "R78")
      (value "91k")
      (footprint "R_0805_A")
      (description "R 100k 5% 125mW 0805")
      (fields (field (name "PART NUMBER") "300 087") (field (name "PUBLISHER") "RKE"))
      (libsource (lib "SMD") (part "Resistor"))
    )
    (comp (ref "R79")
      (value "150k")
      (footprint "R_0805_A")
      (description "R 220R 1% 125mW 0805")
      (fields (field (name "PART NUMBER") "300 917") (field (name "PUBLISHER") "MFL"))
      (libsource (lib "SMD") (part "Resistor"))
    )
    (comp (ref "R80")
      (value "8k2")
      (footprint "R_0805_A")
      (description "R 5k6 1% 125mW 0805")
      (fields (field (name "PART NUMBER") "300 432") (field (name "PUBLISHER") "MFL"))
      (libsource (lib "SMD") (part "Resistor"))
    )
    (comp (ref "R81")
      (value "47k")
      (footprint "R_0805_A")
      (description "R 47k 5% 125mW 0805")
      (fields (field (name "PART NUMBER") "300 084") (field (name "PUBLISHER") "MFL"))
      (libsource (lib "SMD") (part "Resistor"))
    )
    (comp (ref "R82")
      (value "75k")
      (footprint "R_0805_A")
      (description "R 220R 1% 125mW 0805")
      (fields (field (name "PART NUMBER") "300 917") (field (name "PUBLISHER") "MFL"))
      (libsource (lib "SMD") (part "Resistor"))
    )
    (comp (ref "R83")
      (value "22k")
      (footprint "R_0805_A")
      (description "R 27k 5% 125mW 0805")
      (fields (field (name "PART NUMBER") "300 083") (field (name "PUBLISHER") "MFL"))
      (libsource (lib "SMD") (part "Resistor"))
    )
    (comp (ref "R84")
      (value "43R")
      (footprint "R_0805_A")
      (description "R 47R 1% 125mW 0805")
      (fields (field (name "PART NUMBER") "300 070") (field (name "PUBLISHER") "MFL"))
      (libsource (lib "SMD") (part "Resistor"))
    )
    (comp (ref "R85")
      (value "36k")
      (footprint "R_0805_A")
      (description "R 27k 5% 125mW 0805")
      (fields (field (name "PART NUMBER") "300 083") (field (name "PUBLISHER") "MFL"))
      (libsource (lib "SMD") (part "Resistor"))
    )
    (comp (ref "R86")
      (value "240R")
      (footprint "R_0805_A")
      (description "R 220R 1% 125mW 0805")
      (fields (field (name "PART NUMBER") "300 917") (field (name "PUBLISHER") "MFL"))
      (libsource (lib "SMD") (part "Resistor"))
    )
    (comp (ref "R87")
      (value "4k7")
      (footprint "R_0805_A")
      (description "R 27k 5% 125mW 0805")
      (fields (field (name "PART NUMBER") "300 083") (field (name "PUBLISHER") "MFL"))
      (libsource (lib "SMD") (part "Resistor"))
    )
    (comp (ref "R88")
      (value "100k")
      (footprint "R_0805_A")
      (description "R 27k 5% 125mW 0805")
      (fields (field (name "PART NUMBER") "300 083") (field (name "PUBLISHER") "MFL"))
      (libsource (lib "SMD") (part "Resistor"))
    )
    (comp (ref "R89")
      (value "390R")
      (footprint "R_0805_A")
      (description "R 220R 1% 125mW 0805")
      (fields (field (name "PART NUMBER") "300 917") (field (name "PUBLISHER") "MFL"))
      (libsource (lib "SMD") (part "Resistor"))
    )
    (comp (ref "R90")
      (value "100k")
      (footprint "R_0805_A")
      (description "R 27k 5% 125mW 0805")
      (fields (field (name "PART NUMBER") "300 083") (field (name "PUBLISHER") "MFL"))
      (libsource (lib "SMD") (part "Resistor"))
    )
    (comp (ref "R91")
      (value "100k")
      (footprint "R_0805_A")
      (description "R 27k 5% 125mW 0805")
      (fields (field (name "PART NUMBER") "300 083") (field (name "PUBLISHER") "MFL"))
      (libsource (lib "SMD") (part "Resistor"))
    )
    (comp (ref "R92")
      (value "4k7")
      (footprint "R_0805_A")
      (description "R 4k7 1% 125mW 0805")
      (fields (field (name "PART NUMBER") "300 079") (field (name "PUBLISHER") "RKE"))
      (libsource (lib "SMD") (part "Resistor"))
    )
    (comp (ref "R93")
      (value "4k7")
      (footprint "R_0805_A")
      (description "R 4k7 1% 125mW 0805")
      (fields (field (name "PART NUMBER") "300 079") (field (name "PUBLISHER") "RKE"))
      (libsource (lib "SMD") (part "Resistor"))
    )
    (comp (ref "R94")
      (value "4k7")
      (footprint "R_0805_A")
      (description "R 4k7 1% 125mW 0805")
      (fields (field (name "PART NUMBER") "300 079") (field (name "PUBLISHER") "RKE"))
      (libsource (lib "SMD") (part "Resistor"))
    )
    (comp (ref "R95")
      (value "4k7")
      (footprint "R_0805_A")
      (description "R 4k7 1% 125mW 0805")
      (fields (field (name "PART NUMBER") "300 079") (field (name "PUBLISHER") "RKE"))
      (libsource (lib "SMD") (part "Resistor"))
    )
    (comp (ref "R96")
      (value "100k")
      (footprint "R_0805_A")
      (description "R 27k 5% 125mW 0805")
      (fields (field (name "PART NUMBER") "300 083") (field (name "PUBLISHER") "MFL"))
      (libsource (lib "SMD") (part "Resistor"))
    )
    (comp (ref "R97")
      (value "4k7")
      (footprint "R_0805_A")
      (description "R 4k7 1% 125mW 0805")
      (fields (field (name "PART NUMBER") "300 079") (field (name "PUBLISHER") "RKE"))
      (libsource (lib "SMD") (part "Resistor"))
    )
    (comp (ref "R98")
      (value "4k7")
      (footprint "R_0805_A")
      (description "R 4k7 1% 125mW 0805")
      (fields (field (name "PART NUMBER") "300 079") (field (name "PUBLISHER") "RKE"))
      (libsource (lib "SMD") (part "Resistor"))
    )
    (comp (ref "R99")
      (value "100k")
      (footprint "R_0805_A")
      (description "R 27k 5% 125mW 0805")
      (fields (field (name "PART NUMBER") "300 083") (field (name "PUBLISHER") "MFL"))
      (libsource (lib "SMD") (part "Resistor"))
    )
    (comp (ref "R100")
      (value "22k")
      (footprint "R_0805_A")
      (description "R 22k 5% 125mW 0805")
      (fields (field (name "PART NUMBER") "300 082") (field (name "PUBLISHER") "MFL"))
      (libsource (lib "SMD") (part "Resistor"))
    )
    (comp (ref "R101")
      (value "39k")
      (footprint "R_0805_A")
      (description "R 33k 5% 125mW 0805")
      (fields (field (name "PART NUMBER") "300 435") (field (name "PUBLISHER") "MFL"))
      (libsource (lib "SMD") (part "Resistor"))
    )
    (comp (ref "R102")
      (value "11k")
      (footprint "R_0805_A")
      (description "R 10k 1% 125mW 0805")
      (fields (field (name "PART NUMBER") "300 080") (field (name "PUBLISHER") "MFL"))
      (libsource (lib "SMD") (part "Resistor"))
    )
    (comp (ref "R103")
      (value "20k")
      (footprint "R_0805_A")
      (description "R 22k 5% 125mW 0805")
      (fields (field (name "PART NUMBER") "300 082") (field (name "PUBLISHER") "MFL"))
      (libsource (lib "SMD") (part "Resistor"))
    )
    (comp (ref "R104")
      (value "22k")
      (footprint "R_0805_A")
      (description "R 27k 5% 125mW 0805")
      (fields (field (name "PART NUMBER") "300 083") (field (name "PUBLISHER") "MFL"))
      (libsource (lib "SMD") (part "Resistor"))
    )
    (comp (ref "R105")
      (value "36k")
      (footprint "R_0805_A")
      (description "R 27k 5% 125mW 0805")
      (fields (field (name "PART NUMBER") "300 083") (field (name "PUBLISHER") "MFL"))
      (libsource (lib "SMD") (part "Resistor"))
    )
    (comp (ref "R106")
      (value "56R")
      (footprint "R_0805_A")
      (description "R 47R 1% 125mW 0805")
      (fields (field (name "PART NUMBER") "300 070") (field (name "PUBLISHER") "MFL"))
      (libsource (lib "SMD") (part "Resistor"))
    )
    (comp (ref "R107")
      (value "100R")
      (footprint "R_0805_A")
      (description "R 100R 1% 125mW 0805")
      (fields (field (name "PART NUMBER") "300 069") (field (name "PUBLISHER") "RKE"))
      (libsource (lib "SMD") (part "Resistor"))
    )
    (comp (ref "R108")
      (value "4k7")
      (footprint "R_0805_A")
      (description "R 4k7 1% 125mW 0805")
      (fields (field (name "PART NUMBER") "300 079") (field (name "PUBLISHER") "RKE"))
      (libsource (lib "SMD") (part "Resistor"))
    )
    (comp (ref "R109")
      (value "4k7")
      (footprint "R_0805_A")
      (description "R 4k7 1% 125mW 0805")
      (fields (field (name "PART NUMBER") "300 079") (field (name "PUBLISHER") "RKE"))
      (libsource (lib "SMD") (part "Resistor"))
    )
    (comp (ref "R110")
      (value "4k7")
      (footprint "R_0805_A")
      (description "R 4k7 1% 125mW 0805")
      (fields (field (name "PART NUMBER") "300 079") (field (name "PUBLISHER") "RKE"))
      (libsource (lib "SMD") (part "Resistor"))
    )
    (comp (ref "R111")
      (value "4k7")
      (footprint "R_0805_A")
      (description "R 4k7 1% 125mW 0805")
      (fields (field (name "PART NUMBER") "300 079") (field (name "PUBLISHER") "RKE"))
      (libsource (lib "SMD") (part "Resistor"))
    )
    (comp (ref "S1")
      (value "slide")
      (footprint "MSS3")
      (description "S Slide MSS3V 24V/25mA SPDT")
      (fields (field (name "PART NUMBER") "303 022") (field (name "PUBLISHER") "CVI"))
      (libsource (lib "SMD") (part "Switch_Slide_shield"))
    )
    (comp (ref "U1")
      (value "ESP32-DEVKITC-32D")
      (footprint "MODULE_ESP32-DEVKITC-32D")
      (description "EVAL BOARD FOR ESP-WROOM-32")
      (fields (field (name "MF") "Espressif Systems"))
      (libsource (lib "ESP32-DEVKITC-32D") (part "ESP32-DEVKITC-32D"))
    )
  )
  (nets
    (net (code "1") (name "/1.5kHz") (class "Default")
      (node (ref "C20") (pin "1") (pintype "passive"))
      (node (ref "D6") (pin "1") (pinfunction "K_1") (pintype "passive"))
      (node (ref "IC8") (pin "I9") (pinfunction "22_I9") (pintype "input"))
      (node (ref "R27") (pin "2") (pintype "passive"))
    )
    (net (code "2") (name "/1kHz") (class "Default")
      (node (ref "C32") (pin "1") (pintype "passive"))
      (node (ref "D12") (pin "1") (pinfunction "K_1") (pintype "passive"))
      (node (ref "IC8") (pin "I8") (pinfunction "23_I8") (pintype "input"))
      (node (ref "R45") (pin "2") (pintype "passive"))
    )
    (net (code "3") (name "/2kHz") (class "Default")
      (node (ref "C8") (pin "1") (pintype "passive"))
      (node (ref "D1") (pin "1") (pinfunction "K_1") (pintype "passive"))
      (node (ref "IC8") (pin "I10") (pinfunction "21_I10") (pintype "input"))
      (node (ref "R12") (pin "2") (pintype "passive"))
    )
    (net (code "4") (name "/3kHz") (class "Default")
      (node (ref "C64") (pin "1") (pintype "passive"))
      (node (ref "D29") (pin "1") (pinfunction "K_1") (pintype "passive"))
      (node (ref "IC8") (pin "I11") (pinfunction "20_I11") (pintype "input"))
      (node (ref "R104") (pin "2") (pintype "passive"))
    )
    (net (code "5") (name "/4kHz") (class "Default")
      (node (ref "C55") (pin "1") (pintype "passive"))
      (node (ref "D23") (pin "1") (pinfunction "K_1") (pintype "passive"))
      (node (ref "IC8") (pin "I12") (pinfunction "19_I12") (pintype "input"))
      (node (ref "R83") (pin "2") (pintype "passive"))
    )
    (net (code "6") (name "/6kHz") (class "Default")
      (node (ref "C43") (pin "1") (pintype "passive"))
      (node (ref "D17") (pin "1") (pinfunction "K_1") (pintype "passive"))
      (node (ref "IC8") (pin "I13") (pinfunction "18_I13") (pintype "input"))
      (node (ref "R62") (pin "2") (pintype "passive"))
    )
    (net (code "7") (name "/8kHz") (class "Default")
      (node (ref "C31") (pin "1") (pintype "passive"))
      (node (ref "D11") (pin "1") (pinfunction "K_1") (pintype "passive"))
      (node (ref "IC8") (pin "I14") (pinfunction "17_I14") (pintype "input"))
      (node (ref "R44") (pin "2") (pintype "passive"))
    )
    (net (code "8") (name "/12kHz") (class "Default")
      (node (ref "C19") (pin "1") (pintype "passive"))
      (node (ref "D5") (pin "1") (pinfunction "K_1") (pintype "passive"))
      (node (ref "IC8") (pin "I15") (pinfunction "16_I15") (pintype "input"))
      (node (ref "R26") (pin "2") (pintype "passive"))
    )
    (net (code "9") (name "/64Hz") (class "Default")
      (node (ref "C57") (pin "1") (pintype "passive"))
      (node (ref "D25") (pin "1") (pinfunction "K_1") (pintype "passive"))
      (node (ref "IC8") (pin "I0") (pinfunction "9_I0") (pintype "input"))
      (node (ref "R87") (pin "2") (pintype "passive"))
    )
    (net (code "10") (name "/95Hz") (class "Default")
      (node (ref "C45") (pin "1") (pintype "passive"))
      (node (ref "D19") (pin "1") (pinfunction "K_1") (pintype "passive"))
      (node (ref "IC8") (pin "I1") (pinfunction "8_I1") (pintype "input"))
      (node (ref "R66") (pin "2") (pintype "passive"))
    )
    (net (code "11") (name "/125Hz") (class "Default")
      (node (ref "C33") (pin "1") (pintype "passive"))
      (node (ref "D13") (pin "1") (pinfunction "K_1") (pintype "passive"))
      (node (ref "IC8") (pin "I2") (pinfunction "7_I2") (pintype "input"))
      (node (ref "R48") (pin "2") (pintype "passive"))
    )
    (net (code "12") (name "/185Hz") (class "Default")
      (node (ref "C21") (pin "1") (pintype "passive"))
      (node (ref "D7") (pin "1") (pinfunction "K_1") (pintype "passive"))
      (node (ref "IC8") (pin "I3") (pinfunction "6_I3") (pintype "input"))
      (node (ref "R30") (pin "2") (pintype "passive"))
    )
    (net (code "13") (name "/250Hz") (class "Default")
      (node (ref "C9") (pin "1") (pintype "passive"))
      (node (ref "D2") (pin "1") (pinfunction "K_1") (pintype "passive"))
      (node (ref "IC8") (pin "I4") (pinfunction "5_I4") (pintype "input"))
      (node (ref "R14") (pin "2") (pintype "passive"))
    )
    (net (code "14") (name "/375Hz") (class "Default")
      (node (ref "C65") (pin "1") (pintype "passive"))
      (node (ref "D30") (pin "1") (pinfunction "K_1") (pintype "passive"))
      (node (ref "IC8") (pin "I5") (pinfunction "4_I5") (pintype "input"))
      (node (ref "R105") (pin "2") (pintype "passive"))
    )
    (net (code "15") (name "/500Hz") (class "Default")
      (node (ref "C56") (pin "1") (pintype "passive"))
      (node (ref "D24") (pin "1") (pinfunction "K_1") (pintype "passive"))
      (node (ref "IC8") (pin "I6") (pinfunction "3_I6") (pintype "input"))
      (node (ref "R85") (pin "2") (pintype "passive"))
    )
    (net (code "16") (name "/750Hz") (class "Default")
      (node (ref "C44") (pin "1") (pintype "passive"))
      (node (ref "D18") (pin "1") (pinfunction "K_1") (pintype "passive"))
      (node (ref "IC8") (pin "I7") (pinfunction "2_I7") (pintype "input"))
      (node (ref "R63") (pin "2") (pintype "passive"))
    )
    (net (code "17") (name "/ADC_IN") (class "Default")
      (node (ref "R74") (pin "2") (pintype "passive"))
      (node (ref "R77") (pin "1") (pintype "passive"))
      (node (ref "U1") (pin "5") (pinfunction "IO34_5") (pintype "bidirectional"))
    )
    (net (code "18") (name "/MUX_ENABLE") (class "Default")
      (node (ref "IC8") (pin "E") (pinfunction "15_E") (pintype "input"))
      (node (ref "R88") (pin "2") (pintype "passive"))
      (node (ref "U1") (pin "11") (pinfunction "IO27_11") (pintype "bidirectional"))
    )
    (net (code "19") (name "/MUX_OUT") (class "Default")
      (node (ref "IC7") (pin "5") (pinfunction "B+_5") (pintype "input"))
      (node (ref "IC8") (pin "OUT") (pinfunction "1_OUT") (pintype "output"))
      (node (ref "R75") (pin "1") (pintype "passive"))
    )
    (net (code "20") (name "/Rechteck") (class "Default")
      (node (ref "IC1") (pin "1") (pinfunction "Aout_1") (pintype "output"))
      (node (ref "R1") (pin "2") (pintype "passive"))
      (node (ref "R10") (pin "1") (pintype "passive"))
      (node (ref "R102") (pin "1") (pintype "passive"))
      (node (ref "R103") (pin "1") (pintype "passive"))
      (node (ref "R23") (pin "2") (pintype "passive"))
      (node (ref "R24") (pin "1") (pintype "passive"))
      (node (ref "R25") (pin "1") (pintype "passive"))
      (node (ref "R41") (pin "1") (pintype "passive"))
      (node (ref "R42") (pin "1") (pintype "passive"))
      (node (ref "R43") (pin "1") (pintype "passive"))
      (node (ref "R59") (pin "1") (pintype "passive"))
      (node (ref "R60") (pin "1") (pintype "passive"))
      (node (ref "R61") (pin "1") (pintype "passive"))
      (node (ref "R80") (pin "1") (pintype "passive"))
      (node (ref "R81") (pin "1") (pintype "passive"))
      (node (ref "R82") (pin "1") (pintype "passive"))
      (node (ref "R9") (pin "2") (pintype "passive"))
    )
    (net (code "21") (name "/S0") (class "Default")
      (node (ref "IC8") (pin "S0") (pinfunction "10_S0") (pintype "input"))
      (node (ref "R99") (pin "2") (pintype "passive"))
      (node (ref "U1") (pin "7") (pinfunction "IO32_7") (pintype "bidirectional"))
    )
    (net (code "22") (name "/S1") (class "Default")
      (node (ref "IC8") (pin "S1") (pinfunction "11_S1") (pintype "input"))
      (node (ref "R96") (pin "2") (pintype "passive"))
      (node (ref "U1") (pin "8") (pinfunction "IO33_8") (pintype "bidirectional"))
    )
    (net (code "23") (name "/S2") (class "Default")
      (node (ref "IC8") (pin "S2") (pinfunction "14_S2") (pintype "input"))
      (node (ref "R91") (pin "2") (pintype "passive"))
      (node (ref "U1") (pin "9") (pinfunction "IO25_9") (pintype "bidirectional"))
    )
    (net (code "24") (name "/S3") (class "Default")
      (node (ref "IC8") (pin "S3") (pinfunction "13_S3") (pintype "input"))
      (node (ref "R90") (pin "2") (pintype "passive"))
      (node (ref "U1") (pin "10") (pinfunction "IO26_10") (pintype "bidirectional"))
    )
    (net (code "25") (name "/WS2815_PWM") (class "Default")
      (node (ref "J4") (pin "1") (pinfunction "1_1") (pintype "passive"))
      (node (ref "U1") (pin "33") (pinfunction "IO0_33") (pintype "bidirectional"))
    )
    (net (code "26") (name "GND") (class "Default")
      (node (ref "C19") (pin "2") (pintype "passive"))
      (node (ref "C20") (pin "2") (pintype "passive"))
      (node (ref "C21") (pin "2") (pintype "passive"))
      (node (ref "C31") (pin "2") (pintype "passive"))
      (node (ref "C32") (pin "2") (pintype "passive"))
      (node (ref "C33") (pin "2") (pintype "passive"))
      (node (ref "C43") (pin "2") (pintype "passive"))
      (node (ref "C44") (pin "2") (pintype "passive"))
      (node (ref "C45") (pin "2") (pintype "passive"))
      (node (ref "C55") (pin "2") (pintype "passive"))
      (node (ref "C56") (pin "2") (pintype "passive"))
      (node (ref "C57") (pin "2") (pintype "passive"))
      (node (ref "C64") (pin "2") (pintype "passive"))
      (node (ref "C65") (pin "2") (pintype "passive"))
      (node (ref "C8") (pin "2") (pintype "passive"))
      (node (ref "C9") (pin "2") (pintype "passive"))
      (node (ref "D10") (pin "2") (pinfunction "A_2") (pintype "passive"))
      (node (ref "D14") (pin "2") (pinfunction "A_2") (pintype "passive"))
      (node (ref "D15") (pin "2") (pinfunction "A_2") (pintype "passive"))
      (node (ref "D16") (pin "2") (pinfunction "A_2") (pintype "passive"))
      (node (ref "D20") (pin "2") (pinfunction "A_2") (pintype "passive"))
      (node (ref "D21") (pin "2") (pinfunction "A_2") (pintype "passive"))
      (node (ref "D22") (pin "2") (pinfunction "A_2") (pintype "passive"))
      (node (ref "D26") (pin "2") (pinfunction "A_2") (pintype "passive"))
      (node (ref "D27") (pin "2") (pinfunction "A_2") (pintype "passive"))
      (node (ref "D28") (pin "2") (pinfunction "A_2") (pintype "passive"))
      (node (ref "D3") (pin "2") (pinfunction "A_2") (pintype "passive"))
      (node (ref "D31") (pin "2") (pinfunction "A_2") (pintype "passive"))
      (node (ref "D32") (pin "2") (pinfunction "A_2") (pintype "passive"))
      (node (ref "D4") (pin "2") (pinfunction "A_2") (pintype "passive"))
      (node (ref "D8") (pin "2") (pinfunction "A_2") (pintype "passive"))
      (node (ref "D9") (pin "2") (pinfunction "A_2") (pintype "passive"))
      (node (ref "IC1") (pin "4") (pinfunction "V-_4") (pintype "power_in"))
      (node (ref "IC10") (pin "4") (pinfunction "V-_4") (pintype "power_in"))
      (node (ref "IC2") (pin "4") (pinfunction "V-_4") (pintype "power_in"))
      (node (ref "IC3") (pin "4") (pinfunction "V-_4") (pintype "power_in"))
      (node (ref "IC4") (pin "4") (pinfunction "V-_4") (pintype "power_in"))
      (node (ref "IC5") (pin "4") (pinfunction "V-_4") (pintype "power_in"))
      (node (ref "IC6") (pin "4") (pinfunction "V-_4") (pintype "power_in"))
      (node (ref "IC7") (pin "4") (pinfunction "V-_4") (pintype "power_in"))
      (node (ref "IC8") (pin "GND") (pinfunction "12_GND") (pintype "power_in"))
      (node (ref "IC9") (pin "4") (pinfunction "V-_4") (pintype "power_in"))
      (node (ref "J1") (pin "2") (pinfunction "2_2") (pintype "passive"))
      (node (ref "J2") (pin "1") (pinfunction "1_1") (pintype "passive"))
      (node (ref "J3") (pin "1") (pinfunction "1_1") (pintype "passive"))
      (node (ref "R104") (pin "1") (pintype "passive"))
      (node (ref "R105") (pin "1") (pintype "passive"))
      (node (ref "R109") (pin "2") (pintype "passive"))
      (node (ref "R111") (pin "2") (pintype "passive"))
      (node (ref "R12") (pin "1") (pintype "passive"))
      (node (ref "R14") (pin "1") (pintype "passive"))
      (node (ref "R17") (pin "2") (pintype "passive"))
      (node (ref "R19") (pin "2") (pintype "passive"))
      (node (ref "R26") (pin "1") (pintype "passive"))
      (node (ref "R27") (pin "1") (pintype "passive"))
      (node (ref "R30") (pin "1") (pintype "passive"))
      (node (ref "R33") (pin "2") (pintype "passive"))
      (node (ref "R35") (pin "2") (pintype "passive"))
      (node (ref "R37") (pin "2") (pintype "passive"))
      (node (ref "R44") (pin "1") (pintype "passive"))
      (node (ref "R45") (pin "1") (pintype "passive"))
      (node (ref "R48") (pin "1") (pintype "passive"))
      (node (ref "R51") (pin "2") (pintype "passive"))
      (node (ref "R53") (pin "2") (pintype "passive"))
      (node (ref "R55") (pin "2") (pintype "passive"))
      (node (ref "R62") (pin "1") (pintype "passive"))
      (node (ref "R63") (pin "1") (pintype "passive"))
      (node (ref "R66") (pin "1") (pintype "passive"))
      (node (ref "R69") (pin "2") (pintype "passive"))
      (node (ref "R71") (pin "2") (pintype "passive"))
      (node (ref "R73") (pin "2") (pintype "passive"))
      (node (ref "R75") (pin "2") (pintype "passive"))
      (node (ref "R77") (pin "2") (pintype "passive"))
      (node (ref "R8") (pin "2") (pintype "passive"))
      (node (ref "R83") (pin "1") (pintype "passive"))
      (node (ref "R85") (pin "1") (pintype "passive"))
      (node (ref "R87") (pin "1") (pintype "passive"))
      (node (ref "R88") (pin "1") (pintype "passive"))
      (node (ref "R90") (pin "1") (pintype "passive"))
      (node (ref "R91") (pin "1") (pintype "passive"))
      (node (ref "R93") (pin "2") (pintype "passive"))
      (node (ref "R95") (pin "2") (pintype "passive"))
      (node (ref "R96") (pin "1") (pintype "passive"))
      (node (ref "R98") (pin "2") (pintype "passive"))
      (node (ref "R99") (pin "1") (pintype "passive"))
      (node (ref "U1") (pin "14") (pinfunction "GND1_14") (pintype "power_in"))
      (node (ref "U1") (pin "20") (pinfunction "GND3_20") (pintype "power_in"))
      (node (ref "U1") (pin "26") (pinfunction "GND2_26") (pintype "power_in"))
    )
    (net (code "27") (name "Net-(C1-Pad1)") (class "Default")
      (node (ref "C1") (pin "1") (pintype "passive"))
      (node (ref "S1") (pin "1") (pinfunction "A_1") (pintype "passive"))
    )
    (net (code "28") (name "Net-(C1-Pad2)") (class "Default")
      (node (ref "C1") (pin "2") (pintype "passive"))
      (node (ref "R3") (pin "1") (pintype "passive"))
    )
    (net (code "29") (name "Net-(C2-Pad1)") (class "Default")
      (node (ref "C2") (pin "1") (pintype "passive"))
      (node (ref "C6") (pin "1") (pintype "passive"))
      (node (ref "R13") (pin "2") (pintype "passive"))
      (node (ref "R9") (pin "1") (pintype "passive"))
    )
    (net (code "30") (name "Net-(C3-Pad1)") (class "Default")
      (node (ref "C3") (pin "1") (pintype "passive"))
      (node (ref "C7") (pin "1") (pintype "passive"))
      (node (ref "R10") (pin "2") (pintype "passive"))
      (node (ref "R15") (pin "1") (pintype "passive"))
    )
    (net (code "31") (name "Net-(C10-Pad1)") (class "Default")
      (node (ref "C10") (pin "1") (pintype "passive"))
      (node (ref "C17") (pin "1") (pintype "passive"))
      (node (ref "R24") (pin "2") (pintype "passive"))
      (node (ref "R29") (pin "1") (pintype "passive"))
    )
    (net (code "32") (name "Net-(C11-Pad1)") (class "Default")
      (node (ref "C11") (pin "1") (pintype "passive"))
      (node (ref "C16") (pin "1") (pintype "passive"))
      (node (ref "R23") (pin "1") (pintype "passive"))
      (node (ref "R28") (pin "1") (pintype "passive"))
    )
    (net (code "33") (name "Net-(C12-Pad1)") (class "Default")
      (node (ref "C12") (pin "1") (pintype "passive"))
      (node (ref "C18") (pin "1") (pintype "passive"))
      (node (ref "R25") (pin "2") (pintype "passive"))
      (node (ref "R31") (pin "1") (pintype "passive"))
    )
    (net (code "34") (name "Net-(C22-Pad1)") (class "Default")
      (node (ref "C22") (pin "1") (pintype "passive"))
      (node (ref "C28") (pin "1") (pintype "passive"))
      (node (ref "R41") (pin "2") (pintype "passive"))
      (node (ref "R46") (pin "1") (pintype "passive"))
    )
    (net (code "35") (name "Net-(C23-Pad1)") (class "Default")
      (node (ref "C23") (pin "1") (pintype "passive"))
      (node (ref "C29") (pin "1") (pintype "passive"))
      (node (ref "R42") (pin "2") (pintype "passive"))
      (node (ref "R47") (pin "1") (pintype "passive"))
    )
    (net (code "36") (name "Net-(C24-Pad1)") (class "Default")
      (node (ref "C24") (pin "1") (pintype "passive"))
      (node (ref "C30") (pin "1") (pintype "passive"))
      (node (ref "R43") (pin "2") (pintype "passive"))
      (node (ref "R49") (pin "1") (pintype "passive"))
    )
    (net (code "37") (name "Net-(C34-Pad1)") (class "Default")
      (node (ref "C34") (pin "1") (pintype "passive"))
      (node (ref "C40") (pin "1") (pintype "passive"))
      (node (ref "R59") (pin "2") (pintype "passive"))
      (node (ref "R64") (pin "1") (pintype "passive"))
    )
    (net (code "38") (name "Net-(C35-Pad1)") (class "Default")
      (node (ref "C35") (pin "1") (pintype "passive"))
      (node (ref "C41") (pin "1") (pintype "passive"))
      (node (ref "R60") (pin "2") (pintype "passive"))
      (node (ref "R65") (pin "1") (pintype "passive"))
    )
    (net (code "39") (name "Net-(C38-Pad1)") (class "Default")
      (node (ref "C38") (pin "1") (pintype "passive"))
      (node (ref "C42") (pin "1") (pintype "passive"))
      (node (ref "R61") (pin "2") (pintype "passive"))
      (node (ref "R67") (pin "1") (pintype "passive"))
    )
    (net (code "40") (name "Net-(C46-Pad1)") (class "Default")
      (node (ref "C46") (pin "1") (pintype "passive"))
      (node (ref "C52") (pin "1") (pintype "passive"))
      (node (ref "R80") (pin "2") (pintype "passive"))
      (node (ref "R84") (pin "1") (pintype "passive"))
    )
    (net (code "41") (name "Net-(C47-Pad1)") (class "Default")
      (node (ref "C47") (pin "1") (pintype "passive"))
      (node (ref "C53") (pin "1") (pintype "passive"))
      (node (ref "R81") (pin "2") (pintype "passive"))
      (node (ref "R86") (pin "1") (pintype "passive"))
    )
    (net (code "42") (name "Net-(C48-Pad1)") (class "Default")
      (node (ref "C48") (pin "1") (pintype "passive"))
      (node (ref "C54") (pin "1") (pintype "passive"))
      (node (ref "R82") (pin "2") (pintype "passive"))
      (node (ref "R89") (pin "1") (pintype "passive"))
    )
    (net (code "43") (name "Net-(C58-Pad1)") (class "Default")
      (node (ref "C58") (pin "1") (pintype "passive"))
      (node (ref "C63") (pin "1") (pintype "passive"))
      (node (ref "R103") (pin "2") (pintype "passive"))
      (node (ref "R107") (pin "1") (pintype "passive"))
    )
    (net (code "44") (name "Net-(C59-Pad1)") (class "Default")
      (node (ref "C59") (pin "1") (pintype "passive"))
      (node (ref "C62") (pin "1") (pintype "passive"))
      (node (ref "R102") (pin "2") (pintype "passive"))
      (node (ref "R106") (pin "1") (pintype "passive"))
    )
    (net (code "45") (name "Net-(D1-A)") (class "Default")
      (node (ref "C4") (pin "2") (pintype "passive"))
      (node (ref "D1") (pin "2") (pinfunction "A_2") (pintype "passive"))
      (node (ref "D3") (pin "1") (pinfunction "K_1") (pintype "passive"))
    )
    (net (code "46") (name "Net-(D2-A)") (class "Default")
      (node (ref "C5") (pin "2") (pintype "passive"))
      (node (ref "D2") (pin "2") (pinfunction "A_2") (pintype "passive"))
      (node (ref "D4") (pin "1") (pinfunction "K_1") (pintype "passive"))
    )
    (net (code "47") (name "Net-(D5-A)") (class "Default")
      (node (ref "C13") (pin "2") (pintype "passive"))
      (node (ref "D5") (pin "2") (pinfunction "A_2") (pintype "passive"))
      (node (ref "D8") (pin "1") (pinfunction "K_1") (pintype "passive"))
    )
    (net (code "48") (name "Net-(D6-A)") (class "Default")
      (node (ref "C14") (pin "2") (pintype "passive"))
      (node (ref "D6") (pin "2") (pinfunction "A_2") (pintype "passive"))
      (node (ref "D9") (pin "1") (pinfunction "K_1") (pintype "passive"))
    )
    (net (code "49") (name "Net-(D10-K)") (class "Default")
      (node (ref "C15") (pin "2") (pintype "passive"))
      (node (ref "D10") (pin "1") (pinfunction "K_1") (pintype "passive"))
      (node (ref "D7") (pin "2") (pinfunction "A_2") (pintype "passive"))
    )
    (net (code "50") (name "Net-(D11-A)") (class "Default")
      (node (ref "C25") (pin "2") (pintype "passive"))
      (node (ref "D11") (pin "2") (pinfunction "A_2") (pintype "passive"))
      (node (ref "D14") (pin "1") (pinfunction "K_1") (pintype "passive"))
    )
    (net (code "51") (name "Net-(D12-A)") (class "Default")
      (node (ref "C26") (pin "2") (pintype "passive"))
      (node (ref "D12") (pin "2") (pinfunction "A_2") (pintype "passive"))
      (node (ref "D15") (pin "1") (pinfunction "K_1") (pintype "passive"))
    )
    (net (code "52") (name "Net-(D13-A)") (class "Default")
      (node (ref "C27") (pin "2") (pintype "passive"))
      (node (ref "D13") (pin "2") (pinfunction "A_2") (pintype "passive"))
      (node (ref "D16") (pin "1") (pinfunction "K_1") (pintype "passive"))
    )
    (net (code "53") (name "Net-(D17-A)") (class "Default")
      (node (ref "C36") (pin "2") (pintype "passive"))
      (node (ref "D17") (pin "2") (pinfunction "A_2") (pintype "passive"))
      (node (ref "D20") (pin "1") (pinfunction "K_1") (pintype "passive"))
    )
    (net (code "54") (name "Net-(D18-A)") (class "Default")
      (node (ref "C37") (pin "2") (pintype "passive"))
      (node (ref "D18") (pin "2") (pinfunction "A_2") (pintype "passive"))
      (node (ref "D21") (pin "1") (pinfunction "K_1") (pintype "passive"))
    )
    (net (code "55") (name "Net-(D19-A)") (class "Default")
      (node (ref "C39") (pin "2") (pintype "passive"))
      (node (ref "D19") (pin "2") (pinfunction "A_2") (pintype "passive"))
      (node (ref "D22") (pin "1") (pinfunction "K_1") (pintype "passive"))
    )
    (net (code "56") (name "Net-(D23-A)") (class "Default")
      (node (ref "C49") (pin "2") (pintype "passive"))
      (node (ref "D23") (pin "2") (pinfunction "A_2") (pintype "passive"))
      (node (ref "D26") (pin "1") (pinfunction "K_1") (pintype "passive"))
    )
    (net (code "57") (name "Net-(D24-A)") (class "Default")
      (node (ref "C50") (pin "2") (pintype "passive"))
      (node (ref "D24") (pin "2") (pinfunction "A_2") (pintype "passive"))
      (node (ref "D27") (pin "1") (pinfunction "K_1") (pintype "passive"))
    )
    (net (code "58") (name "Net-(D25-A)") (class "Default")
      (node (ref "C51") (pin "2") (pintype "passive"))
      (node (ref "D25") (pin "2") (pinfunction "A_2") (pintype "passive"))
      (node (ref "D28") (pin "1") (pinfunction "K_1") (pintype "passive"))
    )
    (net (code "59") (name "Net-(D29-A)") (class "Default")
      (node (ref "C60") (pin "2") (pintype "passive"))
      (node (ref "D29") (pin "2") (pinfunction "A_2") (pintype "passive"))
      (node (ref "D31") (pin "1") (pinfunction "K_1") (pintype "passive"))
    )
    (net (code "60") (name "Net-(D30-A)") (class "Default")
      (node (ref "C61") (pin "2") (pintype "passive"))
      (node (ref "D30") (pin "2") (pinfunction "A_2") (pintype "passive"))
      (node (ref "D32") (pin "1") (pinfunction "K_1") (pintype "passive"))
    )
    (net (code "61") (name "Net-(IC1A-A+)") (class "Default")
      (node (ref "IC1") (pin "3") (pinfunction "A+_3") (pintype "input"))
      (node (ref "R7") (pin "2") (pintype "passive"))
      (node (ref "R8") (pin "1") (pintype "passive"))
    )
    (net (code "62") (name "Net-(IC1A-A-)") (class "Default")
      (node (ref "IC1") (pin "2") (pinfunction "A-_2") (pintype "input"))
      (node (ref "R1") (pin "1") (pintype "passive"))
      (node (ref "R3") (pin "2") (pintype "passive"))
    )
    (net (code "63") (name "Net-(IC1B-B+)") (class "Default")
      (node (ref "IC1") (pin "5") (pinfunction "B+_5") (pintype "input"))
      (node (ref "R15") (pin "2") (pintype "passive"))
      (node (ref "R18") (pin "2") (pintype "passive"))
      (node (ref "R19") (pin "1") (pintype "passive"))
    )
    (net (code "64") (name "Net-(IC1B-B-)") (class "Default")
      (node (ref "C7") (pin "2") (pintype "passive"))
      (node (ref "IC1") (pin "6") (pinfunction "B-_6") (pintype "input"))
      (node (ref "R6") (pin "1") (pintype "passive"))
    )
    (net (code "65") (name "Net-(IC1B-Bout)") (class "Default")
      (node (ref "C3") (pin "2") (pintype "passive"))
      (node (ref "C5") (pin "1") (pintype "passive"))
      (node (ref "IC1") (pin "7") (pinfunction "Bout_7") (pintype "output"))
      (node (ref "R6") (pin "2") (pintype "passive"))
    )
    (net (code "66") (name "Net-(IC2A-A+)") (class "Default")
      (node (ref "IC2") (pin "3") (pinfunction "A+_3") (pintype "input"))
      (node (ref "R13") (pin "1") (pintype "passive"))
      (node (ref "R16") (pin "2") (pintype "passive"))
      (node (ref "R17") (pin "1") (pintype "passive"))
    )
    (net (code "67") (name "Net-(IC2A-A-)") (class "Default")
      (node (ref "C6") (pin "2") (pintype "passive"))
      (node (ref "IC2") (pin "2") (pinfunction "A-_2") (pintype "input"))
      (node (ref "R4") (pin "1") (pintype "passive"))
    )
    (net (code "68") (name "Net-(IC2A-Aout)") (class "Default")
      (node (ref "C2") (pin "2") (pintype "passive"))
      (node (ref "C4") (pin "1") (pintype "passive"))
      (node (ref "IC2") (pin "1") (pinfunction "Aout_1") (pintype "output"))
      (node (ref "R4") (pin "2") (pintype "passive"))
    )
    (net (code "69") (name "Net-(IC2B-B+)") (class "Default")
      (node (ref "IC2") (pin "5") (pinfunction "B+_5") (pintype "input"))
      (node (ref "R28") (pin "2") (pintype "passive"))
      (node (ref "R32") (pin "2") (pintype "passive"))
      (node (ref "R33") (pin "1") (pintype "passive"))
    )
    (net (code "70") (name "Net-(IC2B-B-)") (class "Default")
      (node (ref "C16") (pin "2") (pintype "passive"))
      (node (ref "IC2") (pin "6") (pinfunction "B-_6") (pintype "input"))
      (node (ref "R20") (pin "1") (pintype "passive"))
    )
    (net (code "71") (name "Net-(IC2B-Bout)") (class "Default")
      (node (ref "C11") (pin "2") (pintype "passive"))
      (node (ref "C13") (pin "1") (pintype "passive"))
      (node (ref "IC2") (pin "7") (pinfunction "Bout_7") (pintype "output"))
      (node (ref "R20") (pin "2") (pintype "passive"))
    )
    (net (code "72") (name "Net-(IC3A-A+)") (class "Default")
      (node (ref "IC3") (pin "3") (pinfunction "A+_3") (pintype "input"))
      (node (ref "R31") (pin "2") (pintype "passive"))
      (node (ref "R36") (pin "2") (pintype "passive"))
      (node (ref "R37") (pin "1") (pintype "passive"))
    )
    (net (code "73") (name "Net-(IC3A-A-)") (class "Default")
      (node (ref "C18") (pin "2") (pintype "passive"))
      (node (ref "IC3") (pin "2") (pinfunction "A-_2") (pintype "input"))
      (node (ref "R22") (pin "1") (pintype "passive"))
    )
    (net (code "74") (name "Net-(IC3A-Aout)") (class "Default")
      (node (ref "C12") (pin "2") (pintype "passive"))
      (node (ref "C15") (pin "1") (pintype "passive"))
      (node (ref "IC3") (pin "1") (pinfunction "Aout_1") (pintype "output"))
      (node (ref "R22") (pin "2") (pintype "passive"))
    )
    (net (code "75") (name "Net-(IC3B-B+)") (class "Default")
      (node (ref "IC3") (pin "5") (pinfunction "B+_5") (pintype "input"))
      (node (ref "R29") (pin "2") (pintype "passive"))
      (node (ref "R34") (pin "2") (pintype "passive"))
      (node (ref "R35") (pin "1") (pintype "passive"))
    )
    (net (code "76") (name "Net-(IC3B-B-)") (class "Default")
      (node (ref "C17") (pin "2") (pintype "passive"))
      (node (ref "IC3") (pin "6") (pinfunction "B-_6") (pintype "input"))
      (node (ref "R21") (pin "1") (pintype "passive"))
    )
    (net (code "77") (name "Net-(IC3B-Bout)") (class "Default")
      (node (ref "C10") (pin "2") (pintype "passive"))
      (node (ref "C14") (pin "1") (pintype "passive"))
      (node (ref "IC3") (pin "7") (pinfunction "Bout_7") (pintype "output"))
      (node (ref "R21") (pin "2") (pintype "passive"))
    )
    (net (code "78") (name "Net-(IC4A-A+)") (class "Default")
      (node (ref "IC4") (pin "3") (pinfunction "A+_3") (pintype "input"))
      (node (ref "R46") (pin "2") (pintype "passive"))
      (node (ref "R50") (pin "2") (pintype "passive"))
      (node (ref "R51") (pin "1") (pintype "passive"))
    )
    (net (code "79") (name "Net-(IC4A-A-)") (class "Default")
      (node (ref "C28") (pin "2") (pintype "passive"))
      (node (ref "IC4") (pin "2") (pinfunction "A-_2") (pintype "input"))
      (node (ref "R38") (pin "2") (pintype "passive"))
    )
    (net (code "80") (name "Net-(IC4A-Aout)") (class "Default")
      (node (ref "C22") (pin "2") (pintype "passive"))
      (node (ref "C25") (pin "1") (pintype "passive"))
      (node (ref "IC4") (pin "1") (pinfunction "Aout_1") (pintype "output"))
      (node (ref "R38") (pin "1") (pintype "passive"))
    )
    (net (code "81") (name "Net-(IC4B-B+)") (class "Default")
      (node (ref "IC4") (pin "5") (pinfunction "B+_5") (pintype "input"))
      (node (ref "R49") (pin "2") (pintype "passive"))
      (node (ref "R54") (pin "2") (pintype "passive"))
      (node (ref "R55") (pin "1") (pintype "passive"))
    )
    (net (code "82") (name "Net-(IC4B-B-)") (class "Default")
      (node (ref "C30") (pin "2") (pintype "passive"))
      (node (ref "IC4") (pin "6") (pinfunction "B-_6") (pintype "input"))
      (node (ref "R40") (pin "1") (pintype "passive"))
    )
    (net (code "83") (name "Net-(IC4B-Bout)") (class "Default")
      (node (ref "C24") (pin "2") (pintype "passive"))
      (node (ref "C27") (pin "1") (pintype "passive"))
      (node (ref "IC4") (pin "7") (pinfunction "Bout_7") (pintype "output"))
      (node (ref "R40") (pin "2") (pintype "passive"))
    )
    (net (code "84") (name "Net-(IC5A-A+)") (class "Default")
      (node (ref "IC5") (pin "3") (pinfunction "A+_3") (pintype "input"))
      (node (ref "R47") (pin "2") (pintype "passive"))
      (node (ref "R52") (pin "2") (pintype "passive"))
      (node (ref "R53") (pin "1") (pintype "passive"))
    )
    (net (code "85") (name "Net-(IC5A-A-)") (class "Default")
      (node (ref "C29") (pin "2") (pintype "passive"))
      (node (ref "IC5") (pin "2") (pinfunction "A-_2") (pintype "input"))
      (node (ref "R39") (pin "1") (pintype "passive"))
    )
    (net (code "86") (name "Net-(IC5A-Aout)") (class "Default")
      (node (ref "C23") (pin "2") (pintype "passive"))
      (node (ref "C26") (pin "1") (pintype "passive"))
      (node (ref "IC5") (pin "1") (pinfunction "Aout_1") (pintype "output"))
      (node (ref "R39") (pin "2") (pintype "passive"))
    )
    (net (code "87") (name "Net-(IC5B-B+)") (class "Default")
      (node (ref "IC5") (pin "5") (pinfunction "B+_5") (pintype "input"))
      (node (ref "R64") (pin "2") (pintype "passive"))
      (node (ref "R68") (pin "2") (pintype "passive"))
      (node (ref "R69") (pin "1") (pintype "passive"))
    )
    (net (code "88") (name "Net-(IC5B-B-)") (class "Default")
      (node (ref "C40") (pin "2") (pintype "passive"))
      (node (ref "IC5") (pin "6") (pinfunction "B-_6") (pintype "input"))
      (node (ref "R56") (pin "1") (pintype "passive"))
    )
    (net (code "89") (name "Net-(IC5B-Bout)") (class "Default")
      (node (ref "C34") (pin "2") (pintype "passive"))
      (node (ref "C36") (pin "1") (pintype "passive"))
      (node (ref "IC5") (pin "7") (pinfunction "Bout_7") (pintype "output"))
      (node (ref "R56") (pin "2") (pintype "passive"))
    )
    (net (code "90") (name "Net-(IC6A-A+)") (class "Default")
      (node (ref "IC6") (pin "3") (pinfunction "A+_3") (pintype "input"))
      (node (ref "R67") (pin "2") (pintype "passive"))
      (node (ref "R72") (pin "2") (pintype "passive"))
      (node (ref "R73") (pin "1") (pintype "passive"))
    )
    (net (code "91") (name "Net-(IC6A-A-)") (class "Default")
      (node (ref "C42") (pin "2") (pintype "passive"))
      (node (ref "IC6") (pin "2") (pinfunction "A-_2") (pintype "input"))
      (node (ref "R58") (pin "1") (pintype "passive"))
    )
    (net (code "92") (name "Net-(IC6A-Aout)") (class "Default")
      (node (ref "C38") (pin "2") (pintype "passive"))
      (node (ref "C39") (pin "1") (pintype "passive"))
      (node (ref "IC6") (pin "1") (pinfunction "Aout_1") (pintype "output"))
      (node (ref "R58") (pin "2") (pintype "passive"))
    )
    (net (code "93") (name "Net-(IC6B-B+)") (class "Default")
      (node (ref "IC6") (pin "5") (pinfunction "B+_5") (pintype "input"))
      (node (ref "R65") (pin "2") (pintype "passive"))
      (node (ref "R70") (pin "2") (pintype "passive"))
      (node (ref "R71") (pin "1") (pintype "passive"))
    )
    (net (code "94") (name "Net-(IC6B-B-)") (class "Default")
      (node (ref "C41") (pin "2") (pintype "passive"))
      (node (ref "IC6") (pin "6") (pinfunction "B-_6") (pintype "input"))
      (node (ref "R57") (pin "1") (pintype "passive"))
    )
    (net (code "95") (name "Net-(IC6B-Bout)") (class "Default")
      (node (ref "C35") (pin "2") (pintype "passive"))
      (node (ref "C37") (pin "1") (pintype "passive"))
      (node (ref "IC6") (pin "7") (pinfunction "Bout_7") (pintype "output"))
      (node (ref "R57") (pin "2") (pintype "passive"))
    )
    (net (code "96") (name "Net-(IC7A-A+)") (class "Default")
      (node (ref "IC7") (pin "3") (pinfunction "A+_3") (pintype "input"))
      (node (ref "R107") (pin "2") (pintype "passive"))
      (node (ref "R110") (pin "2") (pintype "passive"))
      (node (ref "R111") (pin "1") (pintype "passive"))
    )
    (net (code "97") (name "Net-(IC7A-A-)") (class "Default")
      (node (ref "C63") (pin "2") (pintype "passive"))
      (node (ref "IC7") (pin "2") (pinfunction "A-_2") (pintype "input"))
      (node (ref "R101") (pin "1") (pintype "passive"))
    )
    (net (code "98") (name "Net-(IC7A-Aout)") (class "Default")
      (node (ref "C58") (pin "2") (pintype "passive"))
      (node (ref "C61") (pin "1") (pintype "passive"))
      (node (ref "IC7") (pin "1") (pinfunction "Aout_1") (pintype "output"))
      (node (ref "R101") (pin "2") (pintype "passive"))
    )
    (net (code "99") (name "Net-(IC7B-B-)") (class "Default")
      (node (ref "IC7") (pin "6") (pinfunction "B-_6") (pintype "input"))
      (node (ref "IC7") (pin "7") (pinfunction "Bout_7") (pintype "output"))
      (node (ref "R74") (pin "1") (pintype "passive"))
    )
    (net (code "100") (name "Net-(IC9A-A+)") (class "Default")
      (node (ref "IC9") (pin "3") (pinfunction "A+_3") (pintype "input"))
      (node (ref "R86") (pin "2") (pintype "passive"))
      (node (ref "R94") (pin "2") (pintype "passive"))
      (node (ref "R95") (pin "1") (pintype "passive"))
    )
    (net (code "101") (name "Net-(IC9A-A-)") (class "Default")
      (node (ref "C53") (pin "2") (pintype "passive"))
      (node (ref "IC9") (pin "2") (pinfunction "A-_2") (pintype "input"))
      (node (ref "R78") (pin "1") (pintype "passive"))
    )
    (net (code "102") (name "Net-(IC9A-Aout)") (class "Default")
      (node (ref "C47") (pin "2") (pintype "passive"))
      (node (ref "C50") (pin "1") (pintype "passive"))
      (node (ref "IC9") (pin "1") (pinfunction "Aout_1") (pintype "output"))
      (node (ref "R78") (pin "2") (pintype "passive"))
    )
    (net (code "103") (name "Net-(IC9B-B+)") (class "Default")
      (node (ref "IC9") (pin "5") (pinfunction "B+_5") (pintype "input"))
      (node (ref "R89") (pin "2") (pintype "passive"))
      (node (ref "R97") (pin "2") (pintype "passive"))
      (node (ref "R98") (pin "1") (pintype "passive"))
    )
    (net (code "104") (name "Net-(IC9B-B-)") (class "Default")
      (node (ref "C54") (pin "2") (pintype "passive"))
      (node (ref "IC9") (pin "6") (pinfunction "B-_6") (pintype "input"))
      (node (ref "R79") (pin "1") (pintype "passive"))
    )
    (net (code "105") (name "Net-(IC9B-Bout)") (class "Default")
      (node (ref "C48") (pin "2") (pintype "passive"))
      (node (ref "C51") (pin "1") (pintype "passive"))
      (node (ref "IC9") (pin "7") (pinfunction "Bout_7") (pintype "output"))
      (node (ref "R79") (pin "2") (pintype "passive"))
    )
    (net (code "106") (name "Net-(IC10A-A+)") (class "Default")
      (node (ref "IC10") (pin "3") (pinfunction "A+_3") (pintype "input"))
      (node (ref "R84") (pin "2") (pintype "passive"))
      (node (ref "R92") (pin "2") (pintype "passive"))
      (node (ref "R93") (pin "1") (pintype "passive"))
    )
    (net (code "107") (name "Net-(IC10A-A-)") (class "Default")
      (node (ref "C52") (pin "2") (pintype "passive"))
      (node (ref "IC10") (pin "2") (pinfunction "A-_2") (pintype "input"))
      (node (ref "R76") (pin "1") (pintype "passive"))
    )
    (net (code "108") (name "Net-(IC10A-Aout)") (class "Default")
      (node (ref "C46") (pin "2") (pintype "passive"))
      (node (ref "C49") (pin "1") (pintype "passive"))
      (node (ref "IC10") (pin "1") (pinfunction "Aout_1") (pintype "output"))
      (node (ref "R76") (pin "2") (pintype "passive"))
    )
    (net (code "109") (name "Net-(IC10B-B+)") (class "Default")
      (node (ref "IC10") (pin "5") (pinfunction "B+_5") (pintype "input"))
      (node (ref "R106") (pin "2") (pintype "passive"))
      (node (ref "R108") (pin "2") (pintype "passive"))
      (node (ref "R109") (pin "1") (pintype "passive"))
    )
    (net (code "110") (name "Net-(IC10B-B-)") (class "Default")
      (node (ref "C62") (pin "2") (pintype "passive"))
      (node (ref "IC10") (pin "6") (pinfunction "B-_6") (pintype "input"))
      (node (ref "R100") (pin "1") (pintype "passive"))
    )
    (net (code "111") (name "Net-(IC10B-Bout)") (class "Default")
      (node (ref "C59") (pin "2") (pintype "passive"))
      (node (ref "C60") (pin "1") (pintype "passive"))
      (node (ref "IC10") (pin "7") (pinfunction "Bout_7") (pintype "output"))
      (node (ref "R100") (pin "2") (pintype "passive"))
    )
    (net (code "112") (name "Net-(J3-Pad2)") (class "Default")
      (node (ref "J3") (pin "2") (pinfunction "2_2") (pintype "passive"))
      (node (ref "R5") (pin "2") (pintype "passive"))
    )
    (net (code "113") (name "Net-(J3-Pad3)") (class "Default")
      (node (ref "J3") (pin "3") (pinfunction "3_3") (pintype "passive"))
      (node (ref "R11") (pin "2") (pintype "passive"))
    )
    (net (code "114") (name "Net-(R11-Pad1)") (class "Default")
      (node (ref "R11") (pin "1") (pintype "passive"))
      (node (ref "R5") (pin "1") (pintype "passive"))
      (node (ref "S1") (pin "3") (pinfunction "A_3") (pintype "passive"))
    )
    (net (code "115") (name "Net-(S1-C)") (class "Default")
      (node (ref "J2") (pin "2") (pinfunction "2_2") (pintype "passive"))
      (node (ref "R2") (pin "1") (pintype "passive"))
      (node (ref "S1") (pin "2") (pinfunction "C_2") (pintype "passive"))
    )
    (net (code "116") (name "VCC") (class "Default")
      (node (ref "IC1") (pin "8") (pinfunction "V+_8") (pintype "power_in"))
      (node (ref "IC10") (pin "8") (pinfunction "V+_8") (pintype "power_in"))
      (node (ref "IC2") (pin "8") (pinfunction "V+_8") (pintype "power_in"))
      (node (ref "IC3") (pin "8") (pinfunction "V+_8") (pintype "power_in"))
      (node (ref "IC4") (pin "8") (pinfunction "V+_8") (pintype "power_in"))
      (node (ref "IC5") (pin "8") (pinfunction "V+_8") (pintype "power_in"))
      (node (ref "IC6") (pin "8") (pinfunction "V+_8") (pintype "power_in"))
      (node (ref "IC7") (pin "8") (pinfunction "V+_8") (pintype "power_in"))
      (node (ref "IC8") (pin "VCC") (pinfunction "24_VCC") (pintype "power_in"))
      (node (ref "IC9") (pin "8") (pinfunction "V+_8") (pintype "power_in"))
      (node (ref "J1") (pin "1") (pinfunction "1_1") (pintype "passive"))
      (node (ref "R108") (pin "1") (pintype "passive"))
      (node (ref "R110") (pin "1") (pintype "passive"))
      (node (ref "R16") (pin "1") (pintype "passive"))
      (node (ref "R18") (pin "1") (pintype "passive"))
      (node (ref "R2") (pin "2") (pintype "passive"))
      (node (ref "R32") (pin "1") (pintype "passive"))
      (node (ref "R34") (pin "1") (pintype "passive"))
      (node (ref "R36") (pin "1") (pintype "passive"))
      (node (ref "R50") (pin "1") (pintype "passive"))
      (node (ref "R52") (pin "1") (pintype "passive"))
      (node (ref "R54") (pin "1") (pintype "passive"))
      (node (ref "R68") (pin "1") (pintype "passive"))
      (node (ref "R7") (pin "1") (pintype "passive"))
      (node (ref "R70") (pin "1") (pintype "passive"))
      (node (ref "R72") (pin "1") (pintype "passive"))
      (node (ref "R92") (pin "1") (pintype "passive"))
      (node (ref "R94") (pin "1") (pintype "passive"))
      (node (ref "R97") (pin "1") (pintype "passive"))
      (node (ref "U1") (pin "19") (pinfunction "EXT_5V_19") (pintype "power_in"))
    )
    (net (code "117") (name "unconnected-(S1-PadShield)") (class "Default")
      (node (ref "S1") (pin "Shield") (pintype "passive"))
    )
    (net (code "118") (name "unconnected-(U1-3V3-Pad1)") (class "Default")
      (node (ref "U1") (pin "1") (pinfunction "3V3_1") (pintype "power_in+no_connect"))
    )
    (net (code "119") (name "unconnected-(U1-CLK-Pad38)") (class "Default")
      (node (ref "U1") (pin "38") (pinfunction "CLK_38") (pintype "input+no_connect"))
    )
    (net (code "120") (name "unconnected-(U1-CMD-Pad18)") (class "Default")
      (node (ref "U1") (pin "18") (pinfunction "CMD_18") (pintype "bidirectional+no_connect"))
    )
    (net (code "121") (name "unconnected-(U1-EN-Pad2)") (class "Default")
      (node (ref "U1") (pin "2") (pinfunction "EN_2") (pintype "input+no_connect"))
    )
    (net (code "122") (name "unconnected-(U1-IO2-Pad34)") (class "Default")
      (node (ref "U1") (pin "34") (pinfunction "IO2_34") (pintype "bidirectional+no_connect"))
    )
    (net (code "123") (name "unconnected-(U1-IO4-Pad32)") (class "Default")
      (node (ref "U1") (pin "32") (pinfunction "IO4_32") (pintype "bidirectional+no_connect"))
    )
    (net (code "124") (name "unconnected-(U1-IO5-Pad29)") (class "Default")
      (node (ref "U1") (pin "29") (pinfunction "IO5_29") (pintype "bidirectional+no_connect"))
    )
    (net (code "125") (name "unconnected-(U1-IO12-Pad13)") (class "Default")
      (node (ref "U1") (pin "13") (pinfunction "IO12_13") (pintype "bidirectional+no_connect"))
    )
    (net (code "126") (name "unconnected-(U1-IO13-Pad15)") (class "Default")
      (node (ref "U1") (pin "15") (pinfunction "IO13_15") (pintype "bidirectional+no_connect"))
    )
    (net (code "127") (name "unconnected-(U1-IO14-Pad12)") (class "Default")
      (node (ref "U1") (pin "12") (pinfunction "IO14_12") (pintype "bidirectional+no_connect"))
    )
    (net (code "128") (name "unconnected-(U1-IO15-Pad35)") (class "Default")
      (node (ref "U1") (pin "35") (pinfunction "IO15_35") (pintype "bidirectional+no_connect"))
    )
    (net (code "129") (name "unconnected-(U1-IO16-Pad31)") (class "Default")
      (node (ref "U1") (pin "31") (pinfunction "IO16_31") (pintype "bidirectional+no_connect"))
    )
    (net (code "130") (name "unconnected-(U1-IO17-Pad30)") (class "Default")
      (node (ref "U1") (pin "30") (pinfunction "IO17_30") (pintype "bidirectional+no_connect"))
    )
    (net (code "131") (name "unconnected-(U1-IO18-Pad28)") (class "Default")
      (node (ref "U1") (pin "28") (pinfunction "IO18_28") (pintype "bidirectional+no_connect"))
    )
    (net (code "132") (name "unconnected-(U1-IO19-Pad27)") (class "Default")
      (node (ref "U1") (pin "27") (pinfunction "IO19_27") (pintype "bidirectional+no_connect"))
    )
    (net (code "133") (name "unconnected-(U1-IO21-Pad25)") (class "Default")
      (node (ref "U1") (pin "25") (pinfunction "IO21_25") (pintype "bidirectional+no_connect"))
    )
    (net (code "134") (name "unconnected-(U1-IO22-Pad22)") (class "Default")
      (node (ref "U1") (pin "22") (pinfunction "IO22_22") (pintype "bidirectional+no_connect"))
    )
    (net (code "135") (name "unconnected-(U1-IO23-Pad21)") (class "Default")
      (node (ref "U1") (pin "21") (pinfunction "IO23_21") (pintype "bidirectional+no_connect"))
    )
    (net (code "136") (name "unconnected-(U1-IO35-Pad6)") (class "Default")
      (node (ref "U1") (pin "6") (pinfunction "IO35_6") (pintype "bidirectional+no_connect"))
    )
    (net (code "137") (name "unconnected-(U1-RXD0-Pad24)") (class "Default")
      (node (ref "U1") (pin "24") (pinfunction "RXD0_24") (pintype "input+no_connect"))
    )
    (net (code "138") (name "unconnected-(U1-SD0-Pad37)") (class "Default")
      (node (ref "U1") (pin "37") (pinfunction "SD0_37") (pintype "bidirectional+no_connect"))
    )
    (net (code "139") (name "unconnected-(U1-SD1-Pad36)") (class "Default")
      (node (ref "U1") (pin "36") (pinfunction "SD1_36") (pintype "bidirectional+no_connect"))
    )
    (net (code "140") (name "unconnected-(U1-SD2-Pad16)") (class "Default")
      (node (ref "U1") (pin "16") (pinfunction "SD2_16") (pintype "bidirectional+no_connect"))
    )
    (net (code "141") (name "unconnected-(U1-SD3-Pad17)") (class "Default")
      (node (ref "U1") (pin "17") (pinfunction "SD3_17") (pintype "bidirectional+no_connect"))
    )
    (net (code "142") (name "unconnected-(U1-SENSOR_VN-Pad4)") (class "Default")
      (node (ref "U1") (pin "4") (pinfunction "SENSOR_VN_4") (pintype "input+no_connect"))
    )
    (net (code "143") (name "unconnected-(U1-SENSOR_VP-Pad3)") (class "Default")
      (node (ref "U1") (pin "3") (pinfunction "SENSOR_VP_3") (pintype "input+no_connect"))
    )
    (net (code "144") (name "unconnected-(U1-TXD0-Pad23)") (class "Default")
      (node (ref "U1") (pin "23") (pinfunction "TXD0_23") (pintype "output+no_connect"))
    )
  )
)
